# secs_q84_v2.net
KiCad netlist of a schematic drawn in EAGLE
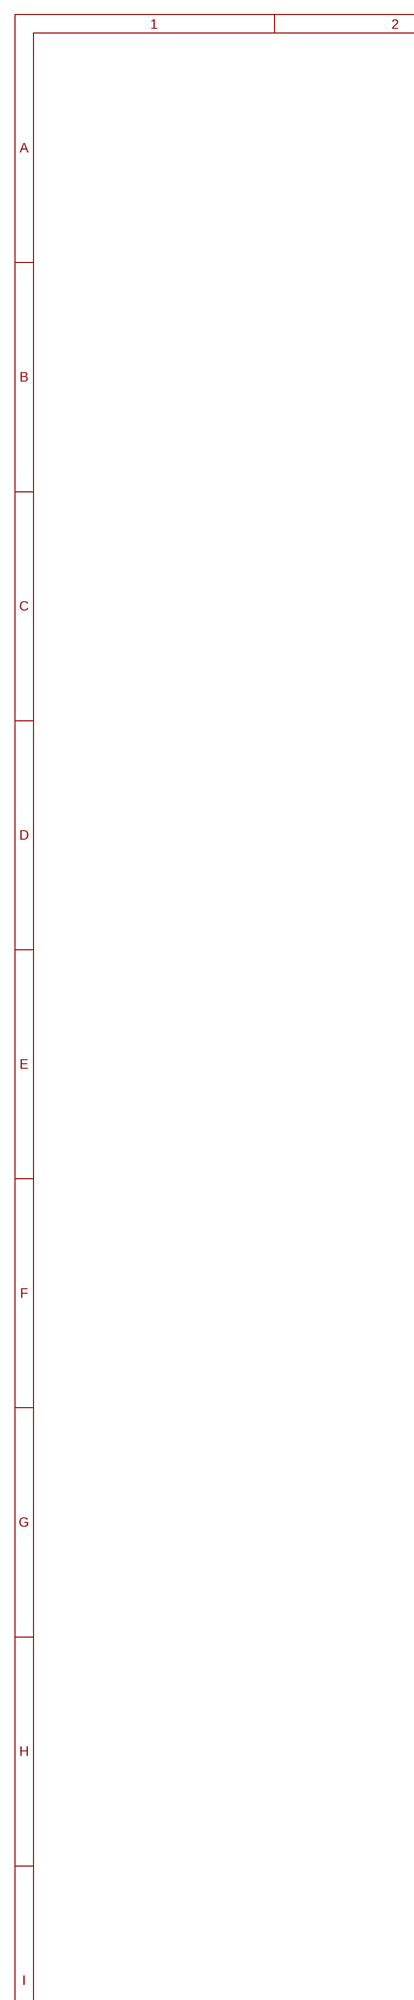
[diagram p0: schematic, sheet 1, part 1 of 2]
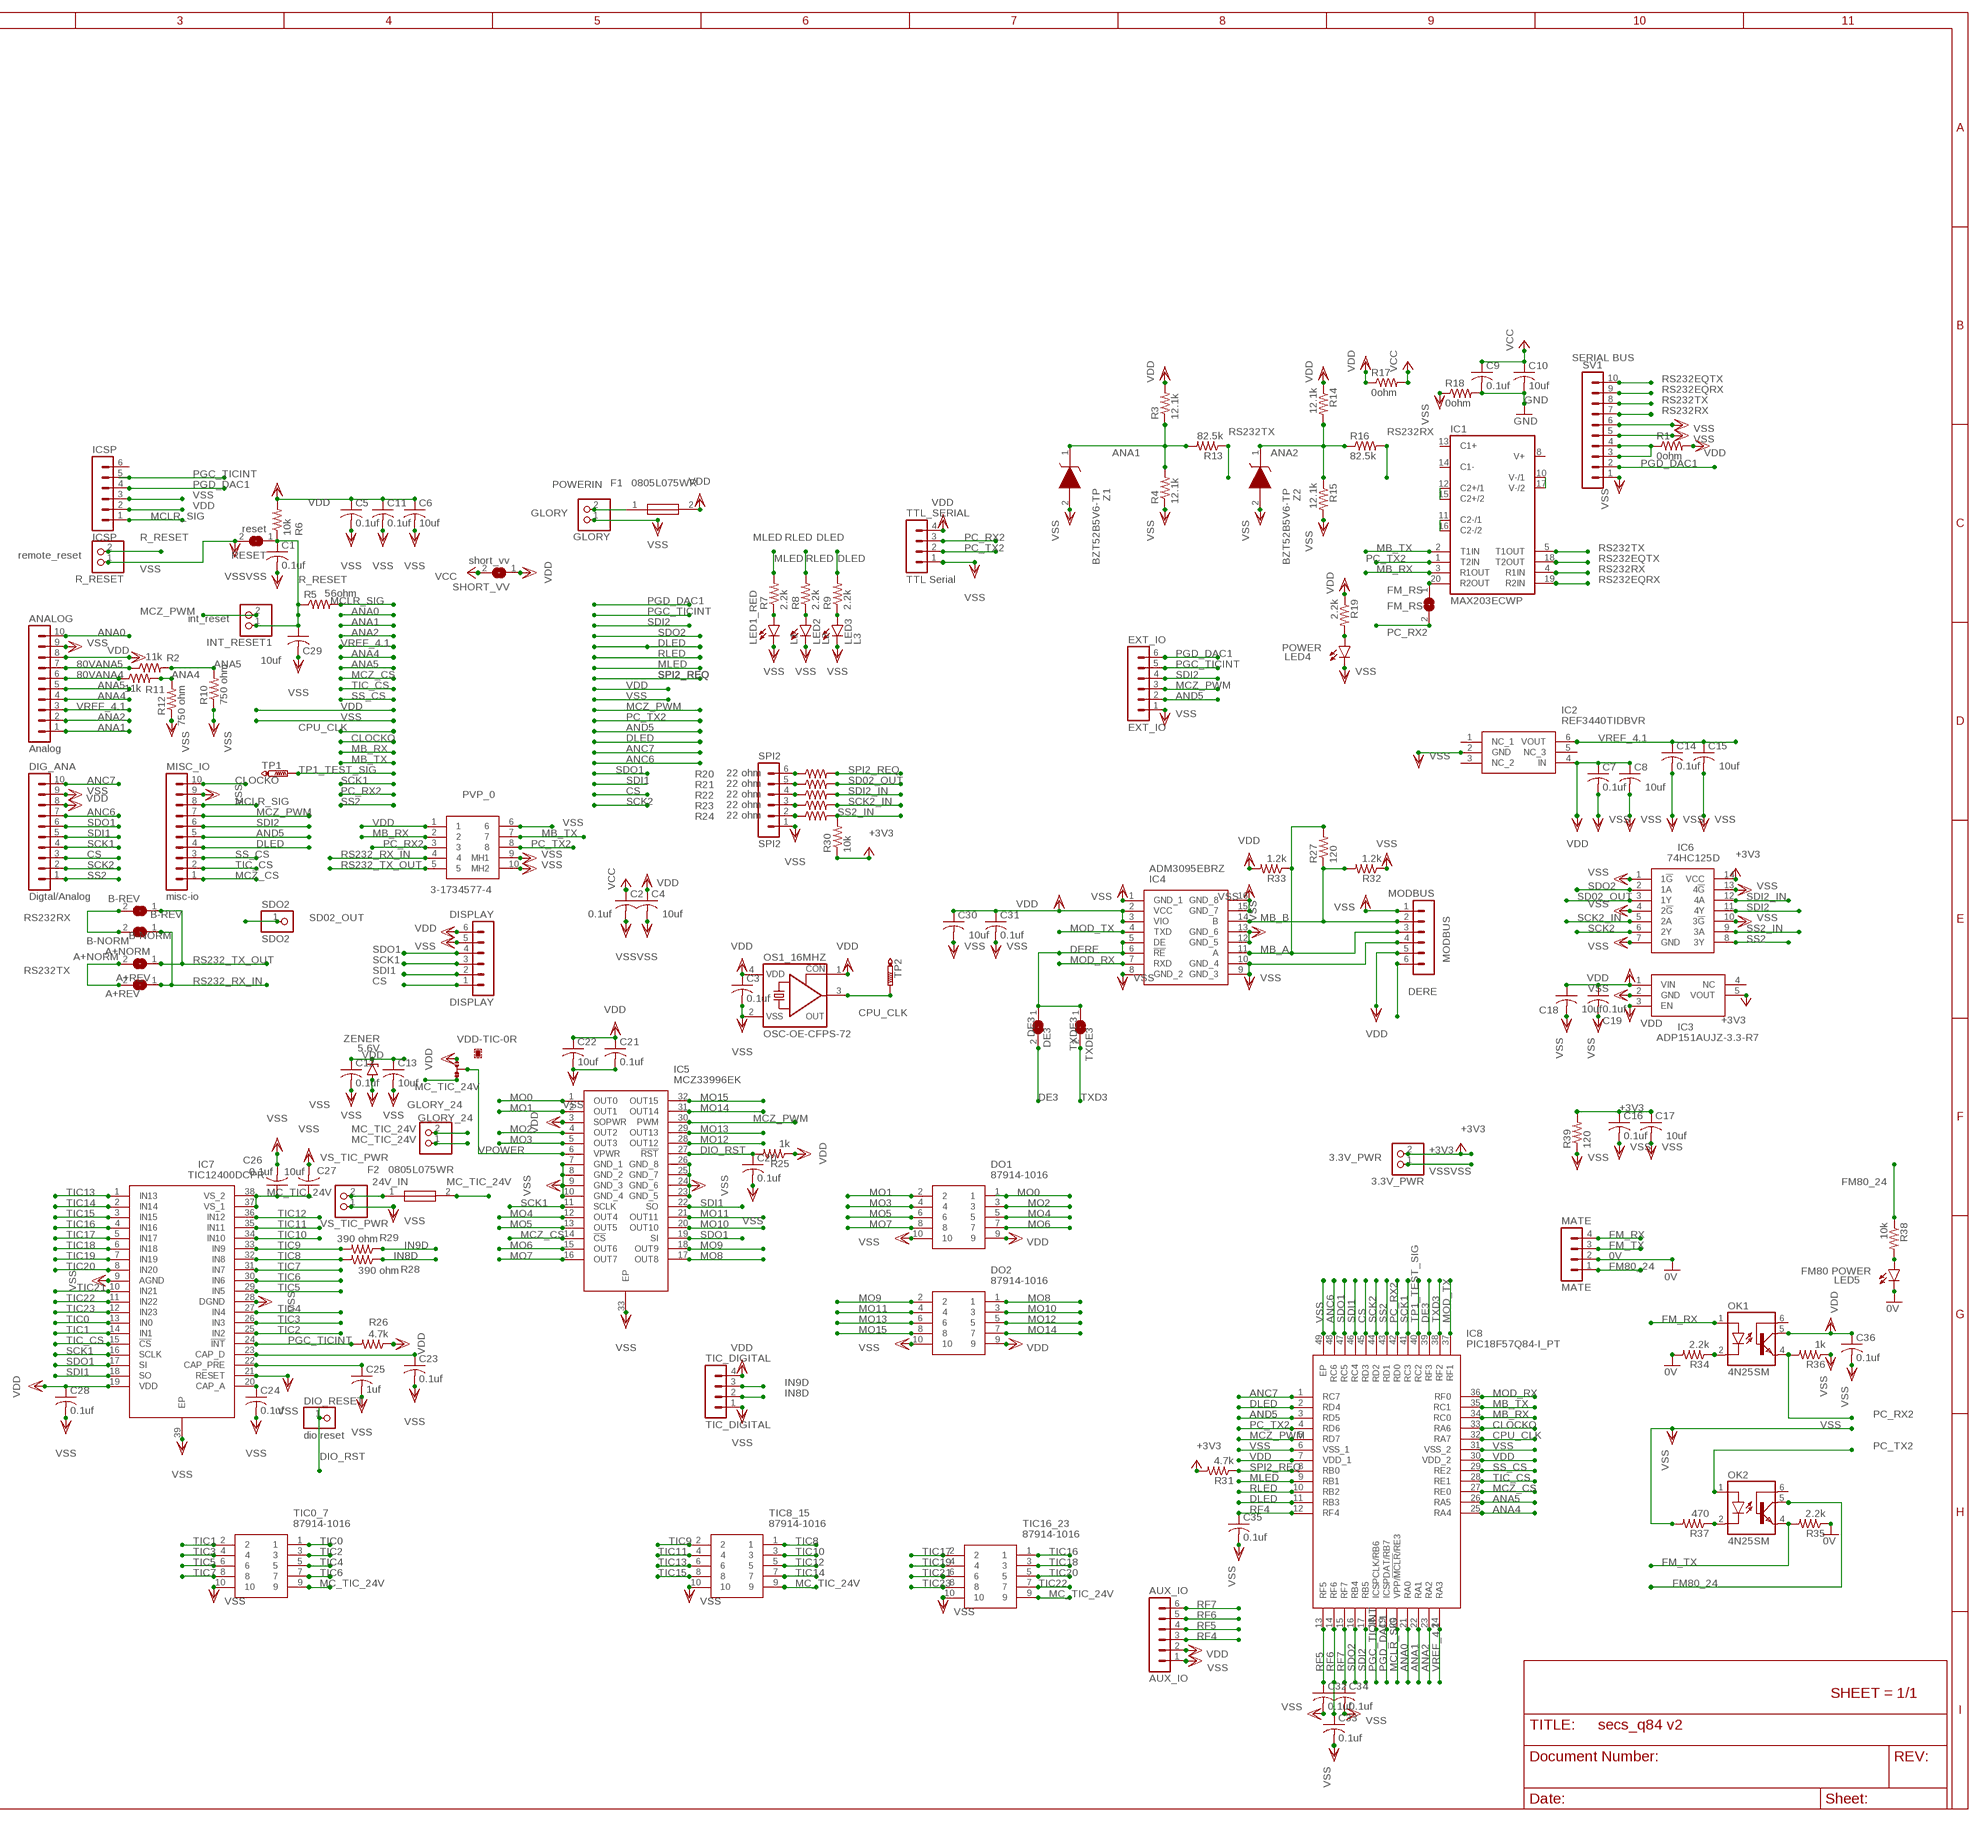
[diagram p1: schematic, sheet 1, part 2 of 2]

(export (version "E")
  (design (tool "Eeschema 10.0.6"))
  (components
    (comp (ref "3.3V_PWR")
      (value "3.3V_PWR")
      (footprint "eagle-import:1X02")
      (libsource (lib "eagle-import") (part "PINHD-1X2"))
    )
    (comp (ref "A+NORM")
      (value "A+NORM")
      (footprint "eagle-import:SJ")
      (libsource (lib "eagle-import") (part "SJ"))
    )
    (comp (ref "A+REV")
      (value "A+REV")
      (footprint "eagle-import:SJ")
      (libsource (lib "eagle-import") (part "SJ"))
    )
    (comp (ref "ANALOG")
      (value "Analog")
      (footprint "eagle-import:MA10-1")
      (libsource (lib "eagle-import") (part "MA10-1"))
    )
    (comp (ref "AUX_IO")
      (value "AUX_IO")
      (footprint "eagle-import:MA06-1")
      (libsource (lib "eagle-import") (part "MA06-1"))
    )
    (comp (ref "B-NORM")
      (value "B-NORM")
      (footprint "eagle-import:SJ")
      (libsource (lib "eagle-import") (part "SJ"))
    )
    (comp (ref "B-REV")
      (value "B-REV")
      (footprint "eagle-import:SJ")
      (libsource (lib "eagle-import") (part "SJ"))
    )
    (comp (ref "C1")
      (value "0.1uf")
      (footprint "eagle-import:C0805")
      (libsource (lib "eagle-import") (part "C-USC0805"))
    )
    (comp (ref "C2")
      (value "0.1uf")
      (footprint "eagle-import:C0805")
      (libsource (lib "eagle-import") (part "C-USC0805"))
    )
    (comp (ref "C3")
      (value "0.1uf")
      (footprint "eagle-import:C0805")
      (libsource (lib "eagle-import") (part "C-USC0805"))
    )
    (comp (ref "C4")
      (value "10uf")
      (footprint "eagle-import:C0805")
      (libsource (lib "eagle-import") (part "C-USC0805"))
    )
    (comp (ref "C5")
      (value "0.1uf")
      (footprint "eagle-import:C0805")
      (libsource (lib "eagle-import") (part "C-USC0805"))
    )
    (comp (ref "C6")
      (value "10uf")
      (footprint "eagle-import:C0805")
      (libsource (lib "eagle-import") (part "C-USC0805"))
    )
    (comp (ref "C7")
      (value "0.1uf")
      (footprint "eagle-import:C0805")
      (libsource (lib "eagle-import") (part "C-USC0805"))
    )
    (comp (ref "C8")
      (value "10uf")
      (footprint "eagle-import:C0805")
      (libsource (lib "eagle-import") (part "C-USC0805"))
    )
    (comp (ref "C9")
      (value "0.1uf")
      (footprint "eagle-import:C0805")
      (libsource (lib "eagle-import") (part "C-USC0805"))
    )
    (comp (ref "C10")
      (value "10uf")
      (footprint "eagle-import:C0805")
      (libsource (lib "eagle-import") (part "C-USC0805"))
    )
    (comp (ref "C11")
      (value "0.1uf")
      (footprint "eagle-import:C0805")
      (libsource (lib "eagle-import") (part "C-USC0805"))
    )
    (comp (ref "C12")
      (value "0.1uf")
      (footprint "eagle-import:C0805")
      (libsource (lib "eagle-import") (part "C-USC0805"))
    )
    (comp (ref "C13")
      (value "10uf")
      (footprint "eagle-import:C0805")
      (libsource (lib "eagle-import") (part "C-USC0805"))
    )
    (comp (ref "C14")
      (value "0.1uf")
      (footprint "eagle-import:C0805")
      (libsource (lib "eagle-import") (part "C-USC0805"))
    )
    (comp (ref "C15")
      (value "10uf")
      (footprint "eagle-import:C0805")
      (libsource (lib "eagle-import") (part "C-USC0805"))
    )
    (comp (ref "C16")
      (value "0.1uf")
      (footprint "eagle-import:C0805")
      (libsource (lib "eagle-import") (part "C-USC0805"))
    )
    (comp (ref "C17")
      (value "10uf")
      (footprint "eagle-import:C0805")
      (libsource (lib "eagle-import") (part "C-USC0805"))
    )
    (comp (ref "C18")
      (value "10uf")
      (footprint "eagle-import:C0805")
      (libsource (lib "eagle-import") (part "C-USC0805"))
    )
    (comp (ref "C19")
      (value "0.1uf")
      (footprint "eagle-import:C0805")
      (libsource (lib "eagle-import") (part "C-USC0805"))
    )
    (comp (ref "C20")
      (value "0.1uf")
      (footprint "eagle-import:C0805")
      (libsource (lib "eagle-import") (part "C-USC0805"))
    )
    (comp (ref "C21")
      (value "0.1uf")
      (footprint "eagle-import:C0805")
      (libsource (lib "eagle-import") (part "C-USC0805"))
    )
    (comp (ref "C22")
      (value "10uf")
      (footprint "eagle-import:C0805")
      (libsource (lib "eagle-import") (part "C-USC0805"))
    )
    (comp (ref "C23")
      (value "0.1uf")
      (footprint "eagle-import:C0805")
      (libsource (lib "eagle-import") (part "C-USC0805"))
    )
    (comp (ref "C24")
      (value "0.1uf")
      (footprint "eagle-import:C0805")
      (libsource (lib "eagle-import") (part "C-USC0805"))
    )
    (comp (ref "C25")
      (value "1uf")
      (footprint "eagle-import:C0805")
      (libsource (lib "eagle-import") (part "C-USC0805"))
    )
    (comp (ref "C26")
      (value "0.1uf")
      (footprint "eagle-import:C0805")
      (libsource (lib "eagle-import") (part "C-USC0805"))
    )
    (comp (ref "C27")
      (value "10uf")
      (footprint "eagle-import:C0805")
      (libsource (lib "eagle-import") (part "C-USC0805"))
    )
    (comp (ref "C28")
      (value "0.1uf")
      (footprint "eagle-import:C0805")
      (libsource (lib "eagle-import") (part "C-USC0805"))
    )
    (comp (ref "C29")
      (value "10uf")
      (footprint "eagle-import:C0805")
      (libsource (lib "eagle-import") (part "C-USC0805"))
    )
    (comp (ref "C30")
      (value "10uf")
      (footprint "eagle-import:C0805")
      (libsource (lib "eagle-import") (part "C-USC0805"))
    )
    (comp (ref "C31")
      (value "0.1uf")
      (footprint "eagle-import:C0805")
      (libsource (lib "eagle-import") (part "C-USC0805"))
    )
    (comp (ref "C32")
      (value "0.1uf")
      (footprint "eagle-import:C0603")
      (libsource (lib "eagle-import") (part "C-USC0603"))
    )
    (comp (ref "C33")
      (value "0.1uf")
      (footprint "eagle-import:C0603")
      (libsource (lib "eagle-import") (part "C-USC0603"))
    )
    (comp (ref "C34")
      (value "0.1uf")
      (footprint "eagle-import:C0603")
      (libsource (lib "eagle-import") (part "C-USC0603"))
    )
    (comp (ref "C35")
      (value "0.1uf")
      (footprint "eagle-import:C0603")
      (libsource (lib "eagle-import") (part "C-USC0603"))
    )
    (comp (ref "C36")
      (value "0.1uf")
      (footprint "eagle-import:C0603")
      (libsource (lib "eagle-import") (part "C-USC0603"))
    )
    (comp (ref "DE3")
      (value "DE3")
      (footprint "eagle-import:SJ")
      (libsource (lib "eagle-import") (part "SJ"))
    )
    (comp (ref "DIG_ANA")
      (value "Digtal/Analog")
      (footprint "eagle-import:MA10-1")
      (libsource (lib "eagle-import") (part "MA10-1"))
    )
    (comp (ref "DIO_RESET")
      (value "dio reset")
      (footprint "eagle-import:1X01")
      (libsource (lib "eagle-import") (part "PINHD-1X1"))
    )
    (comp (ref "DISPLAY")
      (value "DISPLAY")
      (footprint "eagle-import:MA06-1")
      (libsource (lib "eagle-import") (part "MA06-1"))
    )
    (comp (ref "DO1")
      (value "87914-1016")
      (footprint "eagle-import:879141016")
      (fields (field (name "MOUSER_PART_NUMBER") "538-87914-1016"))
      (libsource (lib "eagle-import") (part "87914-1016"))
    )
    (comp (ref "DO2")
      (value "87914-1016")
      (footprint "eagle-import:879141016")
      (fields (field (name "MOUSER_PART_NUMBER") "538-87914-1016"))
      (libsource (lib "eagle-import") (part "87914-1016"))
    )
    (comp (ref "EXT_IO")
      (value "EXT_IO")
      (footprint "eagle-import:MA06-1")
      (libsource (lib "eagle-import") (part "MA06-1"))
    )
    (comp (ref "F1")
      (value "0805L075WR")
      (footprint "eagle-import:FUSC2114X125N")
      (fields (field (name "MOUSER_PART_NUMBER") "576-0805L075WR"))
      (libsource (lib "eagle-import") (part "0805L075WR"))
    )
    (comp (ref "F2")
      (value "0805L075WR")
      (footprint "eagle-import:FUSC2114X125N")
      (fields (field (name "MOUSER_PART_NUMBER") "576-0805L075WR"))
      (libsource (lib "eagle-import") (part "0805L075WR"))
    )
    (comp (ref "FM_RS")
      (value "FM_RS")
      (footprint "eagle-import:SJ")
      (libsource (lib "eagle-import") (part "SJ"))
    )
    (comp (ref "GLORY")
      (value "GLORY")
      (footprint "eagle-import:1X02")
      (libsource (lib "eagle-import") (part "PINHD-1X2"))
    )
    (comp (ref "GLORY_24")
      (value "GLORY_24")
      (footprint "eagle-import:1X02")
      (libsource (lib "eagle-import") (part "PINHD-1X2"))
    )
    (comp (ref "IC1")
      (value "MAX203ECWP")
      (footprint "eagle-import:SO20L")
      (fields (field (name "MPN") "MAX203ECWP+G36"))
      (libsource (lib "eagle-import") (part "MAX203ECWP"))
    )
    (comp (ref "IC2")
      (value "REF3440TIDBVR")
      (footprint "eagle-import:SOT95P280X145-6N")
      (fields (field (name "MOUSER_PART_NUMBER") "595-REF3440TIDBVR"))
      (libsource (lib "eagle-import") (part "REF3440TIDBVR"))
    )
    (comp (ref "IC3")
      (value "ADP151AUJZ-3.3-R7")
      (footprint "eagle-import:SOT95P280X100-5N")
      (fields (field (name "MOUSER_PART_NUMBER") "584-ADP151AUJZ-3.3R7"))
      (libsource (lib "eagle-import") (part "ADP151AUJZ-3.3-R7"))
    )
    (comp (ref "IC4")
      (value "ADM3095EBRZ")
      (footprint "eagle-import:SOIC127P600X175-16N")
      (fields (field (name "MOUSER_PART_NUMBER") "584-ADM3095EBRZ"))
      (libsource (lib "eagle-import") (part "ADM3095EBRZ"))
    )
    (comp (ref "IC5")
      (value "MCZ33996EK")
      (footprint "eagle-import:SOP65P1030X265-33N")
      (fields (field (name "MOUSER_PART_NUMBER") "841-MCZ33996EK"))
      (libsource (lib "eagle-import") (part "MCZ33996EK"))
    )
    (comp (ref "IC6")
      (value "74HC125D")
      (footprint "eagle-import:SOIC127P600X175-14N")
      (fields (field (name "MOUSER_PART_NUMBER") "757-74HC125D"))
      (libsource (lib "eagle-import") (part "74HC125D"))
    )
    (comp (ref "IC7")
      (value "TIC12400DCPR")
      (footprint "eagle-import:SOP50P640X120-39N")
      (fields (field (name "MOUSER_PART_NUMBER") "595-TIC12400DCPR"))
      (libsource (lib "eagle-import") (part "TIC12400DCPR"))
    )
    (comp (ref "IC8")
      (value "PIC18F57Q84-I_PT")
      (footprint "eagle-import:QFP50P900X900X120-49N")
      (fields
        (field (name "MANUFACTURER_PART_NUMBER") "PIC18F57Q84-I/PT")
        (field (name "MOUSER_PART_NUMBER") "579-PIC18F57Q84-I/PT")
      )
      (libsource (lib "eagle-import") (part "PIC18F57Q84-I_PT"))
    )
    (comp (ref "ICSP")
      (value "ICSP")
      (footprint "eagle-import:MA06-1")
      (libsource (lib "eagle-import") (part "MA06-1"))
    )
    (comp (ref "INT_RESET1")
      (value "int_reset")
      (footprint "eagle-import:1X02")
      (libsource (lib "eagle-import") (part "PINHD-1X2"))
    )
    (comp (ref "LED1_RED")
      (value "L1")
      (footprint "eagle-import:CHIPLED_0805")
      (libsource (lib "eagle-import") (part "LEDCHIPLED_0805"))
    )
    (comp (ref "LED2")
      (value "L2")
      (footprint "eagle-import:CHIPLED_0805")
      (libsource (lib "eagle-import") (part "LEDCHIPLED_0805"))
    )
    (comp (ref "LED3")
      (value "L3")
      (footprint "eagle-import:CHIPLED_0805")
      (libsource (lib "eagle-import") (part "LEDCHIPLED_0805"))
    )
    (comp (ref "LED4")
      (value "POWER")
      (footprint "eagle-import:CHIP-LED0603")
      (libsource (lib "eagle-import") (part "LEDCHIP-LED0603"))
    )
    (comp (ref "LED5")
      (value "FM80 POWER")
      (footprint "eagle-import:CHIP-LED0603")
      (libsource (lib "eagle-import") (part "LEDCHIP-LED0603"))
    )
    (comp (ref "MATE")
      (value "MATE")
      (footprint "eagle-import:MA04-1")
      (libsource (lib "eagle-import") (part "MA04-1"))
    )
    (comp (ref "MISC_IO")
      (value "misc-io")
      (footprint "eagle-import:MA10-1")
      (libsource (lib "eagle-import") (part "MA10-1"))
    )
    (comp (ref "MODBUS")
      (value "MODBUS")
      (footprint "eagle-import:MA06-1")
      (libsource (lib "eagle-import") (part "MA06-1"))
    )
    (comp (ref "OK1")
      (value "4N25SM")
      (footprint "eagle-import:DIL6-SMD")
      (fields (field (name "MF") "FAIRCHILD SEMICONDUCTOR"))
      (libsource (lib "eagle-import") (part "4N?MS25"))
    )
    (comp (ref "OK2")
      (value "4N25SM")
      (footprint "eagle-import:DIL6-SMD")
      (fields (field (name "MF") "FAIRCHILD SEMICONDUCTOR"))
      (libsource (lib "eagle-import") (part "4N?MS25"))
    )
    (comp (ref "OS1_16MHZ")
      (value "OSC-OE-CFPS-72")
      (footprint "eagle-import:7.2X5.2-4-PAD")
      (libsource (lib "eagle-import") (part "OSC-OE-CFPS-72"))
    )
    (comp (ref "PVP_0")
      (value "3-1734577-4")
      (footprint "eagle-import:317345774")
      (fields (field (name "MOUSER_PART_NUMBER") "571-3-1734577-4"))
      (libsource (lib "eagle-import") (part "3-1734577-4"))
    )
    (comp (ref "R1")
      (value "0ohm")
      (footprint "eagle-import:R0805")
      (libsource (lib "eagle-import") (part "R-US_R0805"))
    )
    (comp (ref "R2")
      (value "11k")
      (footprint "eagle-import:M1206")
      (libsource (lib "eagle-import") (part "R-US_M1206"))
    )
    (comp (ref "R3")
      (value "12.1k")
      (footprint "eagle-import:R0805")
      (libsource (lib "eagle-import") (part "R-US_R0805"))
    )
    (comp (ref "R4")
      (value "12.1k")
      (footprint "eagle-import:R0805")
      (libsource (lib "eagle-import") (part "R-US_R0805"))
    )
    (comp (ref "R5")
      (value "56ohm")
      (footprint "eagle-import:R0805")
      (libsource (lib "eagle-import") (part "R-US_R0805"))
    )
    (comp (ref "R6")
      (value "10k")
      (footprint "eagle-import:R0805")
      (libsource (lib "eagle-import") (part "R-US_R0805"))
    )
    (comp (ref "R7")
      (value "2.2k")
      (footprint "eagle-import:R0805")
      (libsource (lib "eagle-import") (part "R-US_R0805"))
    )
    (comp (ref "R8")
      (value "2.2k")
      (footprint "eagle-import:R0805")
      (libsource (lib "eagle-import") (part "R-US_R0805"))
    )
    (comp (ref "R9")
      (value "2.2k")
      (footprint "eagle-import:R0805")
      (libsource (lib "eagle-import") (part "R-US_R0805"))
    )
    (comp (ref "R10")
      (value "750 ohm")
      (footprint "eagle-import:M1206")
      (libsource (lib "eagle-import") (part "R-US_M1206"))
    )
    (comp (ref "R11")
      (value "11k")
      (footprint "eagle-import:M1206")
      (libsource (lib "eagle-import") (part "R-US_M1206"))
    )
    (comp (ref "R12")
      (value "750 ohm")
      (footprint "eagle-import:M1206")
      (libsource (lib "eagle-import") (part "R-US_M1206"))
    )
    (comp (ref "R13")
      (value "82.5k")
      (footprint "eagle-import:R0805")
      (libsource (lib "eagle-import") (part "R-US_R0805"))
    )
    (comp (ref "R14")
      (value "12.1k")
      (footprint "eagle-import:R0805")
      (libsource (lib "eagle-import") (part "R-US_R0805"))
    )
    (comp (ref "R15")
      (value "12.1k")
      (footprint "eagle-import:R0805")
      (libsource (lib "eagle-import") (part "R-US_R0805"))
    )
    (comp (ref "R16")
      (value "82.5k")
      (footprint "eagle-import:R0805")
      (libsource (lib "eagle-import") (part "R-US_R0805"))
    )
    (comp (ref "R17")
      (value "0ohm")
      (footprint "eagle-import:R0805")
      (libsource (lib "eagle-import") (part "R-US_R0805"))
    )
    (comp (ref "R18")
      (value "0ohm")
      (footprint "eagle-import:R0805")
      (libsource (lib "eagle-import") (part "R-US_R0805"))
    )
    (comp (ref "R19")
      (value "2.2k")
      (footprint "eagle-import:R0805")
      (libsource (lib "eagle-import") (part "R-US_R0805"))
    )
    (comp (ref "R20")
      (value "22 ohm")
      (footprint "eagle-import:R0805")
      (libsource (lib "eagle-import") (part "R-US_R0805"))
    )
    (comp (ref "R21")
      (value "22 ohm")
      (footprint "eagle-import:R0805")
      (libsource (lib "eagle-import") (part "R-US_R0805"))
    )
    (comp (ref "R22")
      (value "22 ohm")
      (footprint "eagle-import:R0805")
      (libsource (lib "eagle-import") (part "R-US_R0805"))
    )
    (comp (ref "R23")
      (value "22 ohm")
      (footprint "eagle-import:R0805")
      (libsource (lib "eagle-import") (part "R-US_R0805"))
    )
    (comp (ref "R24")
      (value "22 ohm")
      (footprint "eagle-import:R0805")
      (libsource (lib "eagle-import") (part "R-US_R0805"))
    )
    (comp (ref "R25")
      (value "1k")
      (footprint "eagle-import:R0805")
      (libsource (lib "eagle-import") (part "R-US_R0805"))
    )
    (comp (ref "R26")
      (value "4.7k")
      (footprint "eagle-import:R0805")
      (libsource (lib "eagle-import") (part "R-US_R0805"))
    )
    (comp (ref "R27")
      (value "120")
      (footprint "eagle-import:R0805")
      (libsource (lib "eagle-import") (part "R-US_R0805"))
    )
    (comp (ref "R28")
      (value "390 ohm")
      (footprint "eagle-import:R0805")
      (libsource (lib "eagle-import") (part "R-US_R0805"))
    )
    (comp (ref "R29")
      (value "390 ohm")
      (footprint "eagle-import:R0805")
      (libsource (lib "eagle-import") (part "R-US_R0805"))
    )
    (comp (ref "R30")
      (value "10k")
      (footprint "eagle-import:R0805")
      (libsource (lib "eagle-import") (part "R-US_R0805"))
    )
    (comp (ref "R31")
      (value "4.7k")
      (footprint "eagle-import:R0805")
      (libsource (lib "eagle-import") (part "R-US_R0805"))
    )
    (comp (ref "R32")
      (value "1.2k")
      (footprint "eagle-import:R0805")
      (libsource (lib "eagle-import") (part "R-US_R0805"))
    )
    (comp (ref "R33")
      (value "1.2k")
      (footprint "eagle-import:R0805")
      (libsource (lib "eagle-import") (part "R-US_R0805"))
    )
    (comp (ref "R34")
      (value "2.2k")
      (footprint "eagle-import:R0805")
      (libsource (lib "eagle-import") (part "R-US_R0805"))
    )
    (comp (ref "R35")
      (value "2.2k")
      (footprint "eagle-import:R0805")
      (libsource (lib "eagle-import") (part "R-US_R0805"))
    )
    (comp (ref "R36")
      (value "1k")
      (footprint "eagle-import:R0805")
      (libsource (lib "eagle-import") (part "R-US_R0805"))
    )
    (comp (ref "R37")
      (value "470")
      (footprint "eagle-import:R0805")
      (libsource (lib "eagle-import") (part "R-US_R0805"))
    )
    (comp (ref "R38")
      (value "10k")
      (footprint "eagle-import:R0805")
      (libsource (lib "eagle-import") (part "R-US_R0805"))
    )
    (comp (ref "R39")
      (value "120")
      (footprint "eagle-import:R0805")
      (libsource (lib "eagle-import") (part "R-US_R0805"))
    )
    (comp (ref "RESET")
      (value "reset")
      (footprint "eagle-import:SJ")
      (libsource (lib "eagle-import") (part "SJ"))
    )
    (comp (ref "R_RESET")
      (value "remote_reset")
      (footprint "eagle-import:1X02")
      (libsource (lib "eagle-import") (part "PINHD-1X2"))
    )
    (comp (ref "SDO2")
      (value "SDO2")
      (footprint "eagle-import:1X01")
      (libsource (lib "eagle-import") (part "PINHD-1X1"))
    )
    (comp (ref "SHORT_VV")
      (value "short_vv")
      (footprint "eagle-import:SJ")
      (libsource (lib "eagle-import") (part "SJ"))
    )
    (comp (ref "SPI2")
      (value "SPI2")
      (footprint "eagle-import:MA06-1")
      (libsource (lib "eagle-import") (part "MA06-1"))
    )
    (comp (ref "SV1")
      (value "SERIAL BUS")
      (footprint "eagle-import:MA10-1")
      (libsource (lib "eagle-import") (part "MA10-1"))
    )
    (comp (ref "TIC0_7")
      (value "87914-1016")
      (footprint "eagle-import:879141016")
      (fields (field (name "MOUSER_PART_NUMBER") "538-87914-1016"))
      (libsource (lib "eagle-import") (part "87914-1016"))
    )
    (comp (ref "TIC8_15")
      (value "87914-1016")
      (footprint "eagle-import:879141016")
      (fields (field (name "MOUSER_PART_NUMBER") "538-87914-1016"))
      (libsource (lib "eagle-import") (part "87914-1016"))
    )
    (comp (ref "TIC16_23")
      (value "87914-1016")
      (footprint "eagle-import:879141016")
      (fields (field (name "MOUSER_PART_NUMBER") "538-87914-1016"))
      (libsource (lib "eagle-import") (part "87914-1016"))
    )
    (comp (ref "TIC_DIGITAL")
      (value "TIC_DIGITAL")
      (footprint "eagle-import:MA04-1")
      (libsource (lib "eagle-import") (part "MA04-1"))
    )
    (comp (ref "TP1")
      (value "PTR1PAD1-13")
      (footprint "eagle-import:P1-13")
      (libsource (lib "eagle-import") (part "PTR1PAD1-13"))
    )
    (comp (ref "TP2")
      (value "PTR1PAD1-13")
      (footprint "eagle-import:P1-13")
      (libsource (lib "eagle-import") (part "PTR1PAD1-13"))
    )
    (comp (ref "TTL_SERIAL")
      (value "TTL Serial")
      (footprint "eagle-import:MA04-1")
      (libsource (lib "eagle-import") (part "MA04-1"))
    )
    (comp (ref "TXDE3")
      (value "TXDE3")
      (footprint "eagle-import:SJ")
      (libsource (lib "eagle-import") (part "SJ"))
    )
    (comp (ref "VDD-TIC")
      (value "0R-JUMPA")
      (footprint "eagle-import:A0R-JMP")
      (libsource (lib "eagle-import") (part "0R-JUMPA"))
    )
    (comp (ref "VS_TIC_PWR")
      (value "VS_TIC_PWR")
      (footprint "eagle-import:1X02")
      (libsource (lib "eagle-import") (part "PINHD-1X2"))
    )
    (comp (ref "Z1")
      (value "BZT52B5V6-TP")
      (footprint "eagle-import:SOD3716X135N")
      (fields (field (name "MOUSER_PART_NUMBER") "833-BZT52B5V6-TP"))
      (libsource (lib "eagle-import") (part "BZT52B5V6-TP"))
    )
    (comp (ref "Z2")
      (value "BZT52B5V6-TP")
      (footprint "eagle-import:SOD3716X135N")
      (fields (field (name "MOUSER_PART_NUMBER") "833-BZT52B5V6-TP"))
      (libsource (lib "eagle-import") (part "BZT52B5V6-TP"))
    )
    (comp (ref "ZENER")
      (value "5.6V")
      (footprint "eagle-import:SMB")
      (libsource (lib "eagle-import") (part "ZENER-DIODESMB"))
    )
  )
  (nets
    (net (code "1") (name "+3V3") (class "Default")
      (node (ref "3.3V_PWR") (pin "2") (pinfunction "2_2") (pintype "passive"))
      (node (ref "C16") (pin "1") (pinfunction "1_1") (pintype "passive"))
      (node (ref "C17") (pin "1") (pinfunction "1_1") (pintype "passive"))
      (node (ref "IC3") (pin "5") (pinfunction "VOUT_5") (pintype "bidirectional"))
      (node (ref "IC6") (pin "14") (pinfunction "VCC_14") (pintype "bidirectional"))
      (node (ref "R30") (pin "1") (pinfunction "1_1") (pintype "passive"))
      (node (ref "R31") (pin "2") (pinfunction "2_2") (pintype "passive"))
      (node (ref "R39") (pin "2") (pinfunction "2_2") (pintype "passive"))
    )
    (net (code "2") (name "/24V_IN") (class "Default")
      (node (ref "F2") (pin "1") (pinfunction "1_1") (pintype "bidirectional"))
      (node (ref "VS_TIC_PWR") (pin "2") (pinfunction "2_2") (pintype "passive"))
    )
    (net (code "3") (name "/80VANA4") (class "Default")
      (node (ref "ANALOG") (pin "6") (pinfunction "6_6") (pintype "passive"))
      (node (ref "R11") (pin "1") (pinfunction "1_1") (pintype "passive"))
    )
    (net (code "4") (name "/80VANA5") (class "Default")
      (node (ref "ANALOG") (pin "7") (pinfunction "7_7") (pintype "passive"))
      (node (ref "R2") (pin "1") (pinfunction "1_1") (pintype "passive"))
    )
    (net (code "5") (name "/ANA0") (class "Default")
      (node (ref "ANALOG") (pin "10") (pinfunction "10_10") (pintype "passive"))
      (node (ref "IC8") (pin "21") (pinfunction "RA0_21") (pintype "bidirectional"))
    )
    (net (code "6") (name "/ANA1") (class "Default")
      (node (ref "ANALOG") (pin "1") (pinfunction "1_1") (pintype "passive"))
      (node (ref "IC8") (pin "22") (pinfunction "RA1_22") (pintype "bidirectional"))
      (node (ref "R13") (pin "2") (pinfunction "2_2") (pintype "passive"))
      (node (ref "R3") (pin "1") (pinfunction "1_1") (pintype "passive"))
      (node (ref "R4") (pin "2") (pinfunction "2_2") (pintype "passive"))
      (node (ref "Z1") (pin "1") (pinfunction "K_1") (pintype "bidirectional"))
    )
    (net (code "7") (name "/ANA2") (class "Default")
      (node (ref "ANALOG") (pin "2") (pinfunction "2_2") (pintype "passive"))
      (node (ref "IC8") (pin "23") (pinfunction "RA2_23") (pintype "bidirectional"))
      (node (ref "R14") (pin "2") (pinfunction "2_2") (pintype "passive"))
      (node (ref "R15") (pin "1") (pinfunction "1_1") (pintype "passive"))
      (node (ref "R16") (pin "1") (pinfunction "1_1") (pintype "passive"))
      (node (ref "Z2") (pin "1") (pinfunction "K_1") (pintype "bidirectional"))
    )
    (net (code "8") (name "/ANA4") (class "Default")
      (node (ref "ANALOG") (pin "4") (pinfunction "4_4") (pintype "passive"))
      (node (ref "IC8") (pin "25") (pinfunction "RA4_25") (pintype "bidirectional"))
      (node (ref "R11") (pin "2") (pinfunction "2_2") (pintype "passive"))
      (node (ref "R12") (pin "2") (pinfunction "2_2") (pintype "passive"))
    )
    (net (code "9") (name "/ANA5") (class "Default")
      (node (ref "ANALOG") (pin "5") (pinfunction "5_5") (pintype "passive"))
      (node (ref "IC8") (pin "26") (pinfunction "RA5_26") (pintype "bidirectional"))
      (node (ref "R10") (pin "2") (pinfunction "2_2") (pintype "passive"))
      (node (ref "R2") (pin "2") (pinfunction "2_2") (pintype "passive"))
    )
    (net (code "10") (name "/ANC6") (class "Default")
      (node (ref "DIG_ANA") (pin "7") (pinfunction "7_7") (pintype "passive"))
      (node (ref "IC8") (pin "48") (pinfunction "RC6_48") (pintype "bidirectional"))
    )
    (net (code "11") (name "/ANC7") (class "Default")
      (node (ref "DIG_ANA") (pin "10") (pinfunction "10_10") (pintype "passive"))
      (node (ref "IC8") (pin "1") (pinfunction "RC7_1") (pintype "bidirectional"))
    )
    (net (code "12") (name "/AND5") (class "Default")
      (node (ref "EXT_IO") (pin "2") (pinfunction "2_2") (pintype "passive"))
      (node (ref "IC8") (pin "3") (pinfunction "RD5_3") (pintype "bidirectional"))
      (node (ref "MISC_IO") (pin "5") (pinfunction "5_5") (pintype "passive"))
    )
    (net (code "13") (name "/CLOCKO") (class "Default")
      (node (ref "IC8") (pin "33") (pinfunction "RA6_33") (pintype "bidirectional"))
      (node (ref "MISC_IO") (pin "10") (pinfunction "10_10") (pintype "passive"))
    )
    (net (code "14") (name "/CPU_CLK") (class "Default")
      (node (ref "IC8") (pin "32") (pinfunction "RA7_32") (pintype "bidirectional"))
      (node (ref "OS1_16MHZ") (pin "3") (pinfunction "OUT_3") (pintype "output"))
      (node (ref "TP2") (pin "TP") (pinfunction "TP_TP") (pintype "input"))
    )
    (net (code "15") (name "/CS") (class "Default")
      (node (ref "DIG_ANA") (pin "3") (pinfunction "3_3") (pintype "passive"))
      (node (ref "DISPLAY") (pin "1") (pinfunction "1_1") (pintype "passive"))
      (node (ref "IC8") (pin "45") (pinfunction "RD3_45") (pintype "bidirectional"))
    )
    (net (code "16") (name "/DE3") (class "Default")
      (node (ref "DE3") (pin "2") (pinfunction "2_2") (pintype "passive"))
      (node (ref "IC8") (pin "39") (pinfunction "RF3_39") (pintype "bidirectional"))
    )
    (net (code "17") (name "/DERE") (class "Default")
      (node (ref "DE3") (pin "1") (pinfunction "1_1") (pintype "passive"))
      (node (ref "IC4") (pin "5") (pinfunction "DE_5") (pintype "input"))
      (node (ref "IC4") (pin "6") (pinfunction "~{RE}_6") (pintype "input"))
      (node (ref "MODBUS") (pin "6") (pinfunction "6_6") (pintype "passive"))
      (node (ref "TXDE3") (pin "1") (pinfunction "1_1") (pintype "passive"))
    )
    (net (code "18") (name "/DIO_RST") (class "Default")
      (node (ref "C20") (pin "1") (pinfunction "1_1") (pintype "passive"))
      (node (ref "DIO_RESET") (pin "1") (pinfunction "1_1") (pintype "passive"))
      (node (ref "IC5") (pin "27") (pinfunction "~{RST}_27") (pintype "bidirectional"))
      (node (ref "R25") (pin "2") (pinfunction "2_2") (pintype "passive"))
    )
    (net (code "19") (name "/DLED") (class "Default")
      (node (ref "IC8") (pin "11") (pinfunction "RB3_11") (pintype "bidirectional"))
      (node (ref "IC8") (pin "2") (pinfunction "RD4_2") (pintype "bidirectional"))
      (node (ref "MISC_IO") (pin "4") (pinfunction "4_4") (pintype "passive"))
      (node (ref "R9") (pin "2") (pinfunction "2_2") (pintype "passive"))
    )
    (net (code "20") (name "/FM80_24") (class "Default")
      (node (ref "MATE") (pin "1") (pinfunction "1_1") (pintype "passive"))
      (node (ref "OK2") (pin "5") (pinfunction "COL_5") (pintype "passive"))
      (node (ref "R38") (pin "1") (pinfunction "1_1") (pintype "passive"))
    )
    (net (code "21") (name "/FM_RX") (class "Default")
      (node (ref "MATE") (pin "4") (pinfunction "4_4") (pintype "passive"))
      (node (ref "OK1") (pin "1") (pinfunction "A_1") (pintype "passive"))
    )
    (net (code "22") (name "/FM_TX") (class "Default")
      (node (ref "MATE") (pin "3") (pinfunction "3_3") (pintype "passive"))
      (node (ref "OK2") (pin "4") (pinfunction "EMI_4") (pintype "passive"))
      (node (ref "R35") (pin "2") (pinfunction "2_2") (pintype "passive"))
    )
    (net (code "23") (name "/IN8D") (class "Default")
      (node (ref "R28") (pin "1") (pinfunction "1_1") (pintype "passive"))
      (node (ref "TIC_DIGITAL") (pin "2") (pinfunction "2_2") (pintype "passive"))
    )
    (net (code "24") (name "/IN9D") (class "Default")
      (node (ref "R29") (pin "1") (pinfunction "1_1") (pintype "passive"))
      (node (ref "TIC_DIGITAL") (pin "3") (pinfunction "3_3") (pintype "passive"))
    )
    (net (code "25") (name "/MB_A") (class "Default")
      (node (ref "IC4") (pin "11") (pinfunction "A_11") (pintype "bidirectional"))
      (node (ref "MODBUS") (pin "3") (pinfunction "3_3") (pintype "passive"))
      (node (ref "R27") (pin "2") (pinfunction "2_2") (pintype "passive"))
      (node (ref "R33") (pin "1") (pinfunction "1_1") (pintype "passive"))
    )
    (net (code "26") (name "/MB_B") (class "Default")
      (node (ref "IC4") (pin "14") (pinfunction "B_14") (pintype "bidirectional"))
      (node (ref "MODBUS") (pin "2") (pinfunction "2_2") (pintype "passive"))
      (node (ref "R27") (pin "1") (pinfunction "1_1") (pintype "passive"))
      (node (ref "R32") (pin "2") (pinfunction "2_2") (pintype "passive"))
    )
    (net (code "27") (name "/MB_RX") (class "Default")
      (node (ref "IC1") (pin "3") (pinfunction "R1OUT_3") (pintype "output"))
      (node (ref "IC8") (pin "34") (pinfunction "RC0_34") (pintype "bidirectional"))
      (node (ref "PVP_0") (pin "2") (pinfunction "2_2") (pintype "bidirectional"))
    )
    (net (code "28") (name "/MB_TX") (class "Default")
      (node (ref "IC1") (pin "2") (pinfunction "T1IN_2") (pintype "input"))
      (node (ref "IC8") (pin "35") (pinfunction "RC1_35") (pintype "bidirectional"))
      (node (ref "PVP_0") (pin "7") (pinfunction "7_7") (pintype "bidirectional"))
    )
    (net (code "29") (name "/MCLR_SIG") (class "Default")
      (node (ref "IC8") (pin "20") (pinfunction "VPP/~{MCLR}/RE3_20") (pintype "bidirectional"))
      (node (ref "ICSP") (pin "1") (pinfunction "1_1") (pintype "passive"))
      (node (ref "MISC_IO") (pin "8") (pinfunction "8_8") (pintype "passive"))
      (node (ref "R5") (pin "2") (pinfunction "2_2") (pintype "passive"))
    )
    (net (code "30") (name "/MCZ_CS") (class "Default")
      (node (ref "IC5") (pin "14") (pinfunction "~{CS}_14") (pintype "bidirectional"))
      (node (ref "IC8") (pin "27") (pinfunction "RE0_27") (pintype "bidirectional"))
      (node (ref "MISC_IO") (pin "1") (pinfunction "1_1") (pintype "passive"))
    )
    (net (code "31") (name "/MCZ_PWM") (class "Default")
      (node (ref "EXT_IO") (pin "3") (pinfunction "3_3") (pintype "passive"))
      (node (ref "IC5") (pin "30") (pinfunction "PWM_30") (pintype "bidirectional"))
      (node (ref "IC8") (pin "5") (pinfunction "RD7_5") (pintype "bidirectional"))
      (node (ref "INT_RESET1") (pin "2") (pinfunction "2_2") (pintype "passive"))
      (node (ref "MISC_IO") (pin "7") (pinfunction "7_7") (pintype "passive"))
    )
    (net (code "32") (name "/MC_TIC_24V") (class "Default")
      (node (ref "C26") (pin "1") (pinfunction "1_1") (pintype "passive"))
      (node (ref "C27") (pin "1") (pinfunction "1_1") (pintype "passive"))
      (node (ref "F2") (pin "2") (pinfunction "2_2") (pintype "bidirectional"))
      (node (ref "GLORY_24") (pin "1") (pinfunction "1_1") (pintype "passive"))
      (node (ref "GLORY_24") (pin "2") (pinfunction "2_2") (pintype "passive"))
      (node (ref "IC7") (pin "37") (pinfunction "VS_1_37") (pintype "bidirectional"))
      (node (ref "IC7") (pin "38") (pinfunction "VS_2_38") (pintype "bidirectional"))
      (node (ref "TIC0_7") (pin "9") (pinfunction "9_9") (pintype "bidirectional"))
      (node (ref "TIC16_23") (pin "9") (pinfunction "9_9") (pintype "bidirectional"))
      (node (ref "TIC8_15") (pin "9") (pinfunction "9_9") (pintype "bidirectional"))
      (node (ref "VDD-TIC") (pin "3") (pinfunction "3_3") (pintype "passive"))
    )
    (net (code "33") (name "/MLED") (class "Default")
      (node (ref "IC8") (pin "9") (pinfunction "RB1_9") (pintype "bidirectional"))
      (node (ref "R7") (pin "2") (pinfunction "2_2") (pintype "passive"))
    )
    (net (code "34") (name "/MO0") (class "Default")
      (node (ref "DO1") (pin "1") (pinfunction "1_1") (pintype "bidirectional"))
      (node (ref "IC5") (pin "1") (pinfunction "OUT0_1") (pintype "bidirectional"))
    )
    (net (code "35") (name "/MO1") (class "Default")
      (node (ref "DO1") (pin "2") (pinfunction "2_2") (pintype "bidirectional"))
      (node (ref "IC5") (pin "2") (pinfunction "OUT1_2") (pintype "bidirectional"))
    )
    (net (code "36") (name "/MO2") (class "Default")
      (node (ref "DO1") (pin "3") (pinfunction "3_3") (pintype "bidirectional"))
      (node (ref "IC5") (pin "4") (pinfunction "OUT2_4") (pintype "bidirectional"))
    )
    (net (code "37") (name "/MO3") (class "Default")
      (node (ref "DO1") (pin "4") (pinfunction "4_4") (pintype "bidirectional"))
      (node (ref "IC5") (pin "5") (pinfunction "OUT3_5") (pintype "bidirectional"))
    )
    (net (code "38") (name "/MO4") (class "Default")
      (node (ref "DO1") (pin "5") (pinfunction "5_5") (pintype "bidirectional"))
      (node (ref "IC5") (pin "12") (pinfunction "OUT4_12") (pintype "bidirectional"))
    )
    (net (code "39") (name "/MO5") (class "Default")
      (node (ref "DO1") (pin "6") (pinfunction "6_6") (pintype "bidirectional"))
      (node (ref "IC5") (pin "13") (pinfunction "OUT5_13") (pintype "bidirectional"))
    )
    (net (code "40") (name "/MO6") (class "Default")
      (node (ref "DO1") (pin "7") (pinfunction "7_7") (pintype "bidirectional"))
      (node (ref "IC5") (pin "15") (pinfunction "OUT6_15") (pintype "bidirectional"))
    )
    (net (code "41") (name "/MO7") (class "Default")
      (node (ref "DO1") (pin "8") (pinfunction "8_8") (pintype "bidirectional"))
      (node (ref "IC5") (pin "16") (pinfunction "OUT7_16") (pintype "bidirectional"))
    )
    (net (code "42") (name "/MO8") (class "Default")
      (node (ref "DO2") (pin "1") (pinfunction "1_1") (pintype "bidirectional"))
      (node (ref "IC5") (pin "17") (pinfunction "OUT8_17") (pintype "bidirectional"))
    )
    (net (code "43") (name "/MO9") (class "Default")
      (node (ref "DO2") (pin "2") (pinfunction "2_2") (pintype "bidirectional"))
      (node (ref "IC5") (pin "18") (pinfunction "OUT9_18") (pintype "bidirectional"))
    )
    (net (code "44") (name "/MO10") (class "Default")
      (node (ref "DO2") (pin "3") (pinfunction "3_3") (pintype "bidirectional"))
      (node (ref "IC5") (pin "20") (pinfunction "OUT10_20") (pintype "bidirectional"))
    )
    (net (code "45") (name "/MO11") (class "Default")
      (node (ref "DO2") (pin "4") (pinfunction "4_4") (pintype "bidirectional"))
      (node (ref "IC5") (pin "21") (pinfunction "OUT11_21") (pintype "bidirectional"))
    )
    (net (code "46") (name "/MO12") (class "Default")
      (node (ref "DO2") (pin "5") (pinfunction "5_5") (pintype "bidirectional"))
      (node (ref "IC5") (pin "28") (pinfunction "OUT12_28") (pintype "bidirectional"))
    )
    (net (code "47") (name "/MO13") (class "Default")
      (node (ref "DO2") (pin "6") (pinfunction "6_6") (pintype "bidirectional"))
      (node (ref "IC5") (pin "29") (pinfunction "OUT13_29") (pintype "bidirectional"))
    )
    (net (code "48") (name "/MO14") (class "Default")
      (node (ref "DO2") (pin "7") (pinfunction "7_7") (pintype "bidirectional"))
      (node (ref "IC5") (pin "31") (pinfunction "OUT14_31") (pintype "bidirectional"))
    )
    (net (code "49") (name "/MO15") (class "Default")
      (node (ref "DO2") (pin "8") (pinfunction "8_8") (pintype "bidirectional"))
      (node (ref "IC5") (pin "32") (pinfunction "OUT15_32") (pintype "bidirectional"))
    )
    (net (code "50") (name "/MOD_RX") (class "Default")
      (node (ref "IC4") (pin "7") (pinfunction "RXD_7") (pintype "output"))
      (node (ref "IC8") (pin "36") (pinfunction "RF0_36") (pintype "bidirectional"))
    )
    (net (code "51") (name "/MOD_TX") (class "Default")
      (node (ref "IC4") (pin "4") (pinfunction "TXD_4") (pintype "input"))
      (node (ref "IC8") (pin "37") (pinfunction "RF1_37") (pintype "bidirectional"))
    )
    (net (code "52") (name "/PC_RX2") (class "Default")
      (node (ref "FM_RS") (pin "2") (pinfunction "2_2") (pintype "passive"))
      (node (ref "IC8") (pin "42") (pinfunction "RD0_42") (pintype "bidirectional"))
      (node (ref "OK1") (pin "4") (pinfunction "EMI_4") (pintype "passive"))
      (node (ref "PVP_0") (pin "3") (pinfunction "3_3") (pintype "bidirectional"))
      (node (ref "R36") (pin "2") (pinfunction "2_2") (pintype "passive"))
      (node (ref "TTL_SERIAL") (pin "3") (pinfunction "3_3") (pintype "passive"))
    )
    (net (code "53") (name "/PC_TX2") (class "Default")
      (node (ref "IC1") (pin "1") (pinfunction "T2IN_1") (pintype "input"))
      (node (ref "IC8") (pin "4") (pinfunction "RD6_4") (pintype "bidirectional"))
      (node (ref "OK2") (pin "1") (pinfunction "A_1") (pintype "passive"))
      (node (ref "PVP_0") (pin "8") (pinfunction "8_8") (pintype "bidirectional"))
      (node (ref "TTL_SERIAL") (pin "2") (pinfunction "2_2") (pintype "passive"))
    )
    (net (code "54") (name "/PGC_TICINT") (class "Default")
      (node (ref "EXT_IO") (pin "5") (pinfunction "5_5") (pintype "passive"))
      (node (ref "IC7") (pin "24") (pinfunction "~{INT}_24") (pintype "bidirectional"))
      (node (ref "IC8") (pin "18") (pinfunction "ICSPCLK/RB6_18") (pintype "bidirectional"))
      (node (ref "ICSP") (pin "5") (pinfunction "5_5") (pintype "passive"))
      (node (ref "R26") (pin "2") (pinfunction "2_2") (pintype "passive"))
    )
    (net (code "55") (name "/PGD_DAC1") (class "Default")
      (node (ref "EXT_IO") (pin "6") (pinfunction "6_6") (pintype "passive"))
      (node (ref "IC8") (pin "19") (pinfunction "ICSPDAT/RB7_19") (pintype "bidirectional"))
      (node (ref "ICSP") (pin "4") (pinfunction "4_4") (pintype "passive"))
      (node (ref "SV1") (pin "2") (pinfunction "2_2") (pintype "passive"))
    )
    (net (code "56") (name "/POWERIN") (class "Default")
      (node (ref "F1") (pin "1") (pinfunction "1_1") (pintype "bidirectional"))
      (node (ref "GLORY") (pin "2") (pinfunction "2_2") (pintype "passive"))
    )
    (net (code "57") (name "/RF4") (class "Default")
      (node (ref "AUX_IO") (pin "3") (pinfunction "3_3") (pintype "passive"))
      (node (ref "C35") (pin "1") (pinfunction "1_1") (pintype "passive"))
      (node (ref "IC8") (pin "12") (pinfunction "RF4_12") (pintype "bidirectional"))
    )
    (net (code "58") (name "/RF5") (class "Default")
      (node (ref "AUX_IO") (pin "4") (pinfunction "4_4") (pintype "passive"))
      (node (ref "C32") (pin "1") (pinfunction "1_1") (pintype "passive"))
      (node (ref "IC8") (pin "13") (pinfunction "RF5_13") (pintype "bidirectional"))
    )
    (net (code "59") (name "/RF6") (class "Default")
      (node (ref "AUX_IO") (pin "5") (pinfunction "5_5") (pintype "passive"))
      (node (ref "C33") (pin "1") (pinfunction "1_1") (pintype "passive"))
      (node (ref "IC8") (pin "14") (pinfunction "RF6_14") (pintype "bidirectional"))
    )
    (net (code "60") (name "/RF7") (class "Default")
      (node (ref "AUX_IO") (pin "6") (pinfunction "6_6") (pintype "passive"))
      (node (ref "C34") (pin "1") (pinfunction "1_1") (pintype "passive"))
      (node (ref "IC8") (pin "15") (pinfunction "RF7_15") (pintype "bidirectional"))
    )
    (net (code "61") (name "/RLED") (class "Default")
      (node (ref "IC8") (pin "10") (pinfunction "RB2_10") (pintype "bidirectional"))
      (node (ref "R8") (pin "2") (pinfunction "2_2") (pintype "passive"))
    )
    (net (code "62") (name "/RS232EQRX") (class "Default")
      (node (ref "IC1") (pin "19") (pinfunction "R2IN_19") (pintype "input"))
      (node (ref "SV1") (pin "9") (pinfunction "9_9") (pintype "passive"))
    )
    (net (code "63") (name "/RS232EQTX") (class "Default")
      (node (ref "IC1") (pin "18") (pinfunction "T2OUT_18") (pintype "output"))
      (node (ref "SV1") (pin "10") (pinfunction "10_10") (pintype "passive"))
    )
    (net (code "64") (name "/RS232RX") (class "Default")
      (node (ref "B-NORM") (pin "2") (pinfunction "2_2") (pintype "passive"))
      (node (ref "B-REV") (pin "2") (pinfunction "2_2") (pintype "passive"))
      (node (ref "IC1") (pin "4") (pinfunction "R1IN_4") (pintype "input"))
      (node (ref "R16") (pin "2") (pinfunction "2_2") (pintype "passive"))
      (node (ref "SV1") (pin "7") (pinfunction "7_7") (pintype "passive"))
    )
    (net (code "65") (name "/RS232TX") (class "Default")
      (node (ref "A+NORM") (pin "2") (pinfunction "2_2") (pintype "passive"))
      (node (ref "A+REV") (pin "2") (pinfunction "2_2") (pintype "passive"))
      (node (ref "IC1") (pin "5") (pinfunction "T1OUT_5") (pintype "output"))
      (node (ref "R13") (pin "1") (pinfunction "1_1") (pintype "passive"))
      (node (ref "SV1") (pin "8") (pinfunction "8_8") (pintype "passive"))
    )
    (net (code "66") (name "/RS232_RX_IN") (class "Default")
      (node (ref "A+REV") (pin "1") (pinfunction "1_1") (pintype "passive"))
      (node (ref "B-NORM") (pin "1") (pinfunction "1_1") (pintype "passive"))
      (node (ref "PVP_0") (pin "4") (pinfunction "4_4") (pintype "bidirectional"))
    )
    (net (code "67") (name "/RS232_TX_OUT") (class "Default")
      (node (ref "A+NORM") (pin "1") (pinfunction "1_1") (pintype "passive"))
      (node (ref "B-REV") (pin "1") (pinfunction "1_1") (pintype "passive"))
      (node (ref "PVP_0") (pin "5") (pinfunction "5_5") (pintype "bidirectional"))
    )
    (net (code "68") (name "/R_RESET") (class "Default")
      (node (ref "C1") (pin "1") (pinfunction "1_1") (pintype "passive"))
      (node (ref "C29") (pin "1") (pinfunction "1_1") (pintype "passive"))
      (node (ref "INT_RESET1") (pin "1") (pinfunction "1_1") (pintype "passive"))
      (node (ref "R5") (pin "1") (pinfunction "1_1") (pintype "passive"))
      (node (ref "R6") (pin "1") (pinfunction "1_1") (pintype "passive"))
      (node (ref "RESET") (pin "1") (pinfunction "1_1") (pintype "passive"))
      (node (ref "R_RESET") (pin "2") (pinfunction "2_2") (pintype "passive"))
    )
    (net (code "69") (name "/SCK1") (class "Default")
      (node (ref "DIG_ANA") (pin "4") (pinfunction "4_4") (pintype "passive"))
      (node (ref "DISPLAY") (pin "3") (pinfunction "3_3") (pintype "passive"))
      (node (ref "IC5") (pin "11") (pinfunction "SCLK_11") (pintype "bidirectional"))
      (node (ref "IC7") (pin "16") (pinfunction "SCLK_16") (pintype "bidirectional"))
      (node (ref "IC8") (pin "41") (pinfunction "RC3_41") (pintype "bidirectional"))
    )
    (net (code "70") (name "/SCK2") (class "Default")
      (node (ref "DIG_ANA") (pin "2") (pinfunction "2_2") (pintype "passive"))
      (node (ref "IC6") (pin "6") (pinfunction "2Y_6") (pintype "bidirectional"))
      (node (ref "IC8") (pin "44") (pinfunction "RD2_44") (pintype "bidirectional"))
    )
    (net (code "71") (name "/SCK2_IN") (class "Default")
      (node (ref "IC6") (pin "5") (pinfunction "2A_5") (pintype "bidirectional"))
      (node (ref "R23") (pin "2") (pinfunction "2_2") (pintype "passive"))
    )
    (net (code "72") (name "/SD02_OUT") (class "Default")
      (node (ref "IC6") (pin "3") (pinfunction "1Y_3") (pintype "bidirectional"))
      (node (ref "R21") (pin "2") (pinfunction "2_2") (pintype "passive"))
      (node (ref "SDO2") (pin "1") (pinfunction "1_1") (pintype "passive"))
    )
    (net (code "73") (name "/SDI1") (class "Default")
      (node (ref "DIG_ANA") (pin "5") (pinfunction "5_5") (pintype "passive"))
      (node (ref "DISPLAY") (pin "2") (pinfunction "2_2") (pintype "passive"))
      (node (ref "IC5") (pin "22") (pinfunction "SO_22") (pintype "bidirectional"))
      (node (ref "IC7") (pin "18") (pinfunction "SO_18") (pintype "bidirectional"))
      (node (ref "IC8") (pin "46") (pinfunction "RC4_46") (pintype "bidirectional"))
    )
    (net (code "74") (name "/SDI2") (class "Default")
      (node (ref "EXT_IO") (pin "4") (pinfunction "4_4") (pintype "passive"))
      (node (ref "IC6") (pin "11") (pinfunction "4Y_11") (pintype "bidirectional"))
      (node (ref "IC8") (pin "17") (pinfunction "RB5_17") (pintype "bidirectional"))
      (node (ref "MISC_IO") (pin "6") (pinfunction "6_6") (pintype "passive"))
    )
    (net (code "75") (name "/SDI2_IN") (class "Default")
      (node (ref "IC6") (pin "12") (pinfunction "4A_12") (pintype "bidirectional"))
      (node (ref "R22") (pin "2") (pinfunction "2_2") (pintype "passive"))
    )
    (net (code "76") (name "/SDO1") (class "Default")
      (node (ref "DIG_ANA") (pin "6") (pinfunction "6_6") (pintype "passive"))
      (node (ref "DISPLAY") (pin "4") (pinfunction "4_4") (pintype "passive"))
      (node (ref "IC5") (pin "19") (pinfunction "SI_19") (pintype "bidirectional"))
      (node (ref "IC7") (pin "17") (pinfunction "SI_17") (pintype "bidirectional"))
      (node (ref "IC8") (pin "47") (pinfunction "RC5_47") (pintype "bidirectional"))
    )
    (net (code "77") (name "/SDO2") (class "Default")
      (node (ref "IC6") (pin "2") (pinfunction "1A_2") (pintype "bidirectional"))
      (node (ref "IC8") (pin "16") (pinfunction "RB4_16") (pintype "bidirectional"))
    )
    (net (code "78") (name "/SPI2_REQ") (class "Default")
      (node (ref "IC8") (pin "8") (pinfunction "RB0_8") (pintype "bidirectional"))
      (node (ref "R20") (pin "2") (pinfunction "2_2") (pintype "passive"))
      (node (ref "R31") (pin "1") (pinfunction "1_1") (pintype "passive"))
    )
    (net (code "79") (name "/SS2") (class "Default")
      (node (ref "DIG_ANA") (pin "1") (pinfunction "1_1") (pintype "passive"))
      (node (ref "IC6") (pin "8") (pinfunction "3Y_8") (pintype "bidirectional"))
      (node (ref "IC8") (pin "43") (pinfunction "RD1_43") (pintype "bidirectional"))
    )
    (net (code "80") (name "/SS2_IN") (class "Default")
      (node (ref "IC6") (pin "9") (pinfunction "3A_9") (pintype "bidirectional"))
      (node (ref "R24") (pin "2") (pinfunction "2_2") (pintype "passive"))
      (node (ref "R30") (pin "2") (pinfunction "2_2") (pintype "passive"))
    )
    (net (code "81") (name "/SS_CS") (class "Default")
      (node (ref "IC8") (pin "29") (pinfunction "RE2_29") (pintype "bidirectional"))
      (node (ref "MISC_IO") (pin "3") (pinfunction "3_3") (pintype "passive"))
    )
    (net (code "82") (name "/TIC0") (class "Default")
      (node (ref "IC7") (pin "13") (pinfunction "IN0_13") (pintype "bidirectional"))
      (node (ref "TIC0_7") (pin "1") (pinfunction "1_1") (pintype "bidirectional"))
    )
    (net (code "83") (name "/TIC1") (class "Default")
      (node (ref "IC7") (pin "14") (pinfunction "IN1_14") (pintype "bidirectional"))
      (node (ref "TIC0_7") (pin "2") (pinfunction "2_2") (pintype "bidirectional"))
    )
    (net (code "84") (name "/TIC2") (class "Default")
      (node (ref "IC7") (pin "25") (pinfunction "IN2_25") (pintype "bidirectional"))
      (node (ref "TIC0_7") (pin "3") (pinfunction "3_3") (pintype "bidirectional"))
    )
    (net (code "85") (name "/TIC3") (class "Default")
      (node (ref "IC7") (pin "26") (pinfunction "IN3_26") (pintype "bidirectional"))
      (node (ref "TIC0_7") (pin "4") (pinfunction "4_4") (pintype "bidirectional"))
    )
    (net (code "86") (name "/TIC4") (class "Default")
      (node (ref "IC7") (pin "27") (pinfunction "IN4_27") (pintype "bidirectional"))
      (node (ref "TIC0_7") (pin "5") (pinfunction "5_5") (pintype "bidirectional"))
    )
    (net (code "87") (name "/TIC5") (class "Default")
      (node (ref "IC7") (pin "29") (pinfunction "IN5_29") (pintype "bidirectional"))
      (node (ref "TIC0_7") (pin "6") (pinfunction "6_6") (pintype "bidirectional"))
    )
    (net (code "88") (name "/TIC6") (class "Default")
      (node (ref "IC7") (pin "30") (pinfunction "IN6_30") (pintype "bidirectional"))
      (node (ref "TIC0_7") (pin "7") (pinfunction "7_7") (pintype "bidirectional"))
    )
    (net (code "89") (name "/TIC7") (class "Default")
      (node (ref "IC7") (pin "31") (pinfunction "IN7_31") (pintype "bidirectional"))
      (node (ref "TIC0_7") (pin "8") (pinfunction "8_8") (pintype "bidirectional"))
    )
    (net (code "90") (name "/TIC8") (class "Default")
      (node (ref "IC7") (pin "32") (pinfunction "IN8_32") (pintype "bidirectional"))
      (node (ref "R28") (pin "2") (pinfunction "2_2") (pintype "passive"))
      (node (ref "TIC8_15") (pin "1") (pinfunction "1_1") (pintype "bidirectional"))
    )
    (net (code "91") (name "/TIC9") (class "Default")
      (node (ref "IC7") (pin "33") (pinfunction "IN9_33") (pintype "bidirectional"))
      (node (ref "R29") (pin "2") (pinfunction "2_2") (pintype "passive"))
      (node (ref "TIC8_15") (pin "2") (pinfunction "2_2") (pintype "bidirectional"))
    )
    (net (code "92") (name "/TIC10") (class "Default")
      (node (ref "IC7") (pin "34") (pinfunction "IN10_34") (pintype "bidirectional"))
      (node (ref "TIC8_15") (pin "3") (pinfunction "3_3") (pintype "bidirectional"))
    )
    (net (code "93") (name "/TIC11") (class "Default")
      (node (ref "IC7") (pin "35") (pinfunction "IN11_35") (pintype "bidirectional"))
      (node (ref "TIC8_15") (pin "4") (pinfunction "4_4") (pintype "bidirectional"))
    )
    (net (code "94") (name "/TIC12") (class "Default")
      (node (ref "IC7") (pin "36") (pinfunction "IN12_36") (pintype "bidirectional"))
      (node (ref "TIC8_15") (pin "5") (pinfunction "5_5") (pintype "bidirectional"))
    )
    (net (code "95") (name "/TIC13") (class "Default")
      (node (ref "IC7") (pin "1") (pinfunction "IN13_1") (pintype "bidirectional"))
      (node (ref "TIC8_15") (pin "6") (pinfunction "6_6") (pintype "bidirectional"))
    )
    (net (code "96") (name "/TIC14") (class "Default")
      (node (ref "IC7") (pin "2") (pinfunction "IN14_2") (pintype "bidirectional"))
      (node (ref "TIC8_15") (pin "7") (pinfunction "7_7") (pintype "bidirectional"))
    )
    (net (code "97") (name "/TIC15") (class "Default")
      (node (ref "IC7") (pin "3") (pinfunction "IN15_3") (pintype "bidirectional"))
      (node (ref "TIC8_15") (pin "8") (pinfunction "8_8") (pintype "bidirectional"))
    )
    (net (code "98") (name "/TIC16") (class "Default")
      (node (ref "IC7") (pin "4") (pinfunction "IN16_4") (pintype "bidirectional"))
      (node (ref "TIC16_23") (pin "1") (pinfunction "1_1") (pintype "bidirectional"))
    )
    (net (code "99") (name "/TIC17") (class "Default")
      (node (ref "IC7") (pin "5") (pinfunction "IN17_5") (pintype "bidirectional"))
      (node (ref "TIC16_23") (pin "2") (pinfunction "2_2") (pintype "bidirectional"))
    )
    (net (code "100") (name "/TIC18") (class "Default")
      (node (ref "IC7") (pin "6") (pinfunction "IN18_6") (pintype "bidirectional"))
      (node (ref "TIC16_23") (pin "3") (pinfunction "3_3") (pintype "bidirectional"))
    )
    (net (code "101") (name "/TIC19") (class "Default")
      (node (ref "IC7") (pin "7") (pinfunction "IN19_7") (pintype "bidirectional"))
      (node (ref "TIC16_23") (pin "4") (pinfunction "4_4") (pintype "bidirectional"))
    )
    (net (code "102") (name "/TIC20") (class "Default")
      (node (ref "IC7") (pin "8") (pinfunction "IN20_8") (pintype "bidirectional"))
      (node (ref "TIC16_23") (pin "5") (pinfunction "5_5") (pintype "bidirectional"))
    )
    (net (code "103") (name "/TIC21") (class "Default")
      (node (ref "IC7") (pin "10") (pinfunction "IN21_10") (pintype "bidirectional"))
      (node (ref "TIC16_23") (pin "6") (pinfunction "6_6") (pintype "bidirectional"))
    )
    (net (code "104") (name "/TIC22") (class "Default")
      (node (ref "IC7") (pin "11") (pinfunction "IN22_11") (pintype "bidirectional"))
      (node (ref "TIC16_23") (pin "7") (pinfunction "7_7") (pintype "bidirectional"))
    )
    (net (code "105") (name "/TIC23") (class "Default")
      (node (ref "IC7") (pin "12") (pinfunction "IN23_12") (pintype "bidirectional"))
      (node (ref "TIC16_23") (pin "8") (pinfunction "8_8") (pintype "bidirectional"))
    )
    (net (code "106") (name "/TIC_CS") (class "Default")
      (node (ref "IC7") (pin "15") (pinfunction "~{CS}_15") (pintype "bidirectional"))
      (node (ref "IC8") (pin "28") (pinfunction "RE1_28") (pintype "bidirectional"))
      (node (ref "MISC_IO") (pin "2") (pinfunction "2_2") (pintype "passive"))
    )
    (net (code "107") (name "/TP1_TEST_SIG") (class "Default")
      (node (ref "IC8") (pin "40") (pinfunction "RC2_40") (pintype "bidirectional"))
      (node (ref "TP1") (pin "TP") (pinfunction "TP_TP") (pintype "input"))
    )
    (net (code "108") (name "/TXD3") (class "Default")
      (node (ref "IC8") (pin "38") (pinfunction "RF2_38") (pintype "bidirectional"))
      (node (ref "TXDE3") (pin "2") (pinfunction "2_2") (pintype "passive"))
    )
    (net (code "109") (name "/VPOWER") (class "Default")
      (node (ref "IC5") (pin "6") (pinfunction "VPWR_6") (pintype "bidirectional"))
      (node (ref "VDD-TIC") (pin "2") (pinfunction "2_2") (pintype "passive"))
    )
    (net (code "110") (name "/VREF_4.1") (class "Default")
      (node (ref "ANALOG") (pin "3") (pinfunction "3_3") (pintype "passive"))
      (node (ref "C14") (pin "1") (pinfunction "1_1") (pintype "passive"))
      (node (ref "C15") (pin "1") (pinfunction "1_1") (pintype "passive"))
      (node (ref "IC2") (pin "6") (pinfunction "VOUT_6") (pintype "bidirectional"))
      (node (ref "IC8") (pin "24") (pinfunction "RA3_24") (pintype "bidirectional"))
    )
    (net (code "111") (name "0V") (class "Default")
      (node (ref "LED5") (pin "C") (pinfunction "C_C") (pintype "passive"))
      (node (ref "MATE") (pin "2") (pinfunction "2_2") (pintype "passive"))
      (node (ref "R34") (pin "2") (pinfunction "2_2") (pintype "passive"))
      (node (ref "R35") (pin "1") (pinfunction "1_1") (pintype "passive"))
    )
    (net (code "112") (name "GND") (class "Default")
      (node (ref "C10") (pin "2") (pinfunction "2_2") (pintype "passive"))
      (node (ref "C9") (pin "2") (pinfunction "2_2") (pintype "passive"))
      (node (ref "R18") (pin "2") (pinfunction "2_2") (pintype "passive"))
    )
    (net (code "113") (name "Net-(IC1A-C2+{slash}1)") (class "Default")
      (node (ref "IC1") (pin "12") (pinfunction "C2+/1_12") (pintype "passive"))
      (node (ref "IC1") (pin "15") (pinfunction "C2+/2_15") (pintype "passive"))
    )
    (net (code "114") (name "Net-(IC1A-C2-{slash}1)") (class "Default")
      (node (ref "IC1") (pin "11") (pinfunction "C2-/1_11") (pintype "passive"))
      (node (ref "IC1") (pin "16") (pinfunction "C2-/2_16") (pintype "passive"))
    )
    (net (code "115") (name "Net-(IC1A-R2OUT)") (class "Default")
      (node (ref "FM_RS") (pin "1") (pinfunction "1_1") (pintype "passive"))
      (node (ref "IC1") (pin "20") (pinfunction "R2OUT_20") (pintype "output"))
    )
    (net (code "116") (name "Net-(IC1A-V-{slash}1)") (class "Default")
      (node (ref "IC1") (pin "10") (pinfunction "V-/1_10") (pintype "passive"))
      (node (ref "IC1") (pin "17") (pinfunction "V-/2_17") (pintype "passive"))
    )
    (net (code "117") (name "Net-(IC7-CAP_A)") (class "Default")
      (node (ref "C24") (pin "1") (pinfunction "1_1") (pintype "passive"))
      (node (ref "IC7") (pin "20") (pinfunction "CAP_A_20") (pintype "bidirectional"))
    )
    (net (code "118") (name "Net-(IC7-CAP_D)") (class "Default")
      (node (ref "C23") (pin "1") (pinfunction "1_1") (pintype "passive"))
      (node (ref "IC7") (pin "23") (pinfunction "CAP_D_23") (pintype "bidirectional"))
    )
    (net (code "119") (name "Net-(IC7-CAP_PRE)") (class "Default")
      (node (ref "C25") (pin "1") (pinfunction "1_1") (pintype "passive"))
      (node (ref "IC7") (pin "22") (pinfunction "CAP_PRE_22") (pintype "bidirectional"))
    )
    (net (code "120") (name "Net-(LED1_RED-PadA)") (class "Default")
      (node (ref "LED1_RED") (pin "A") (pinfunction "A_A") (pintype "passive"))
      (node (ref "R7") (pin "1") (pinfunction "1_1") (pintype "passive"))
    )
    (net (code "121") (name "Net-(LED2-PadA)") (class "Default")
      (node (ref "LED2") (pin "A") (pinfunction "A_A") (pintype "passive"))
      (node (ref "R8") (pin "1") (pinfunction "1_1") (pintype "passive"))
    )
    (net (code "122") (name "Net-(LED3-PadA)") (class "Default")
      (node (ref "LED3") (pin "A") (pinfunction "A_A") (pintype "passive"))
      (node (ref "R9") (pin "1") (pinfunction "1_1") (pintype "passive"))
    )
    (net (code "123") (name "Net-(LED4-PadA)") (class "Default")
      (node (ref "LED4") (pin "A") (pinfunction "A_A") (pintype "passive"))
      (node (ref "R19") (pin "2") (pinfunction "2_2") (pintype "passive"))
    )
    (net (code "124") (name "Net-(LED5-PadA)") (class "Default")
      (node (ref "LED5") (pin "A") (pinfunction "A_A") (pintype "passive"))
      (node (ref "R38") (pin "2") (pinfunction "2_2") (pintype "passive"))
    )
    (net (code "125") (name "Net-(OK1-C)") (class "Default")
      (node (ref "OK1") (pin "2") (pinfunction "C_2") (pintype "passive"))
      (node (ref "R34") (pin "1") (pinfunction "1_1") (pintype "passive"))
    )
    (net (code "126") (name "Net-(OK2-C)") (class "Default")
      (node (ref "OK2") (pin "2") (pinfunction "C_2") (pintype "passive"))
      (node (ref "R37") (pin "1") (pinfunction "1_1") (pintype "passive"))
    )
    (net (code "127") (name "Net-(R1-Pad1)") (class "Default")
      (node (ref "R1") (pin "1") (pinfunction "1_1") (pintype "passive"))
      (node (ref "SV1") (pin "3") (pinfunction "3_3") (pintype "passive"))
      (node (ref "SV1") (pin "4") (pinfunction "4_4") (pintype "passive"))
    )
    (net (code "128") (name "Net-(R20-Pad1)") (class "Default")
      (node (ref "R20") (pin "1") (pinfunction "1_1") (pintype "passive"))
      (node (ref "SPI2") (pin "6") (pinfunction "6_6") (pintype "passive"))
    )
    (net (code "129") (name "Net-(R21-Pad1)") (class "Default")
      (node (ref "R21") (pin "1") (pinfunction "1_1") (pintype "passive"))
      (node (ref "SPI2") (pin "5") (pinfunction "5_5") (pintype "passive"))
    )
    (net (code "130") (name "Net-(R22-Pad1)") (class "Default")
      (node (ref "R22") (pin "1") (pinfunction "1_1") (pintype "passive"))
      (node (ref "SPI2") (pin "4") (pinfunction "4_4") (pintype "passive"))
    )
    (net (code "131") (name "Net-(R23-Pad1)") (class "Default")
      (node (ref "R23") (pin "1") (pinfunction "1_1") (pintype "passive"))
      (node (ref "SPI2") (pin "3") (pinfunction "3_3") (pintype "passive"))
    )
    (net (code "132") (name "Net-(R24-Pad1)") (class "Default")
      (node (ref "R24") (pin "1") (pinfunction "1_1") (pintype "passive"))
      (node (ref "SPI2") (pin "2") (pinfunction "2_2") (pintype "passive"))
    )
    (net (code "133") (name "VCC") (class "Default")
      (node (ref "C10") (pin "1") (pinfunction "1_1") (pintype "passive"))
      (node (ref "C2") (pin "1") (pinfunction "1_1") (pintype "passive"))
      (node (ref "C9") (pin "1") (pinfunction "1_1") (pintype "passive"))
      (node (ref "R17") (pin "2") (pinfunction "2_2") (pintype "passive"))
      (node (ref "SHORT_VV") (pin "2") (pinfunction "2_2") (pintype "passive"))
    )
    (net (code "134") (name "VDD") (class "Default")
      (node (ref "ANALOG") (pin "8") (pinfunction "8_8") (pintype "passive"))
      (node (ref "AUX_IO") (pin "2") (pinfunction "2_2") (pintype "passive"))
      (node (ref "C11") (pin "1") (pinfunction "1_1") (pintype "passive"))
      (node (ref "C12") (pin "1") (pinfunction "1_1") (pintype "passive"))
      (node (ref "C13") (pin "1") (pinfunction "1_1") (pintype "passive"))
      (node (ref "C18") (pin "1") (pinfunction "1_1") (pintype "passive"))
      (node (ref "C19") (pin "1") (pinfunction "1_1") (pintype "passive"))
      (node (ref "C21") (pin "1") (pinfunction "1_1") (pintype "passive"))
      (node (ref "C22") (pin "1") (pinfunction "1_1") (pintype "passive"))
      (node (ref "C28") (pin "1") (pinfunction "1_1") (pintype "passive"))
      (node (ref "C3") (pin "1") (pinfunction "1_1") (pintype "passive"))
      (node (ref "C30") (pin "1") (pinfunction "1_1") (pintype "passive"))
      (node (ref "C31") (pin "1") (pinfunction "1_1") (pintype "passive"))
      (node (ref "C36") (pin "1") (pinfunction "1_1") (pintype "passive"))
      (node (ref "C4") (pin "1") (pinfunction "1_1") (pintype "passive"))
      (node (ref "C5") (pin "1") (pinfunction "1_1") (pintype "passive"))
      (node (ref "C6") (pin "1") (pinfunction "1_1") (pintype "passive"))
      (node (ref "C7") (pin "1") (pinfunction "1_1") (pintype "passive"))
      (node (ref "C8") (pin "1") (pinfunction "1_1") (pintype "passive"))
      (node (ref "DIG_ANA") (pin "8") (pinfunction "8_8") (pintype "passive"))
      (node (ref "DISPLAY") (pin "6") (pinfunction "6_6") (pintype "passive"))
      (node (ref "DO1") (pin "9") (pinfunction "9_9") (pintype "bidirectional"))
      (node (ref "DO2") (pin "9") (pinfunction "9_9") (pintype "bidirectional"))
      (node (ref "F1") (pin "2") (pinfunction "2_2") (pintype "bidirectional"))
      (node (ref "IC2") (pin "4") (pinfunction "IN_4") (pintype "bidirectional"))
      (node (ref "IC3") (pin "1") (pinfunction "VIN_1") (pintype "bidirectional"))
      (node (ref "IC3") (pin "3") (pinfunction "EN_3") (pintype "bidirectional"))
      (node (ref "IC4") (pin "2") (pinfunction "VCC_2") (pintype "power_in"))
      (node (ref "IC4") (pin "3") (pinfunction "VIO_3") (pintype "power_in"))
      (node (ref "IC5") (pin "3") (pinfunction "SOPWR_3") (pintype "bidirectional"))
      (node (ref "IC7") (pin "19") (pinfunction "VDD_19") (pintype "bidirectional"))
      (node (ref "IC8") (pin "30") (pinfunction "VDD_2_30") (pintype "bidirectional"))
      (node (ref "IC8") (pin "7") (pinfunction "VDD_1_7") (pintype "bidirectional"))
      (node (ref "ICSP") (pin "2") (pinfunction "2_2") (pintype "passive"))
      (node (ref "MODBUS") (pin "5") (pinfunction "5_5") (pintype "passive"))
      (node (ref "OK1") (pin "5") (pinfunction "COL_5") (pintype "passive"))
      (node (ref "OS1_16MHZ") (pin "1") (pinfunction "CON_1") (pintype "input"))
      (node (ref "OS1_16MHZ") (pin "4") (pinfunction "VDD_4") (pintype "power_in"))
      (node (ref "PVP_0") (pin "1") (pinfunction "1_1") (pintype "bidirectional"))
      (node (ref "R1") (pin "2") (pinfunction "2_2") (pintype "passive"))
      (node (ref "R14") (pin "1") (pinfunction "1_1") (pintype "passive"))
      (node (ref "R17") (pin "1") (pinfunction "1_1") (pintype "passive"))
      (node (ref "R19") (pin "1") (pinfunction "1_1") (pintype "passive"))
      (node (ref "R25") (pin "1") (pinfunction "1_1") (pintype "passive"))
      (node (ref "R26") (pin "1") (pinfunction "1_1") (pintype "passive"))
      (node (ref "R3") (pin "2") (pinfunction "2_2") (pintype "passive"))
      (node (ref "R33") (pin "2") (pinfunction "2_2") (pintype "passive"))
      (node (ref "R6") (pin "2") (pinfunction "2_2") (pintype "passive"))
      (node (ref "SHORT_VV") (pin "1") (pinfunction "1_1") (pintype "passive"))
      (node (ref "TIC_DIGITAL") (pin "4") (pinfunction "4_4") (pintype "passive"))
      (node (ref "TTL_SERIAL") (pin "4") (pinfunction "4_4") (pintype "passive"))
      (node (ref "VDD-TIC") (pin "1") (pinfunction "1_1") (pintype "passive"))
      (node (ref "ZENER") (pin "C") (pinfunction "C_C") (pintype "passive"))
    )
    (net (code "135") (name "VSS") (class "Default")
      (node (ref "3.3V_PWR") (pin "1") (pinfunction "1_1") (pintype "passive"))
      (node (ref "ANALOG") (pin "9") (pinfunction "9_9") (pintype "passive"))
      (node (ref "AUX_IO") (pin "1") (pinfunction "1_1") (pintype "passive"))
      (node (ref "C1") (pin "2") (pinfunction "2_2") (pintype "passive"))
      (node (ref "C11") (pin "2") (pinfunction "2_2") (pintype "passive"))
      (node (ref "C12") (pin "2") (pinfunction "2_2") (pintype "passive"))
      (node (ref "C13") (pin "2") (pinfunction "2_2") (pintype "passive"))
      (node (ref "C14") (pin "2") (pinfunction "2_2") (pintype "passive"))
      (node (ref "C15") (pin "2") (pinfunction "2_2") (pintype "passive"))
      (node (ref "C16") (pin "2") (pinfunction "2_2") (pintype "passive"))
      (node (ref "C17") (pin "2") (pinfunction "2_2") (pintype "passive"))
      (node (ref "C18") (pin "2") (pinfunction "2_2") (pintype "passive"))
      (node (ref "C19") (pin "2") (pinfunction "2_2") (pintype "passive"))
      (node (ref "C2") (pin "2") (pinfunction "2_2") (pintype "passive"))
      (node (ref "C20") (pin "2") (pinfunction "2_2") (pintype "passive"))
      (node (ref "C21") (pin "2") (pinfunction "2_2") (pintype "passive"))
      (node (ref "C22") (pin "2") (pinfunction "2_2") (pintype "passive"))
      (node (ref "C23") (pin "2") (pinfunction "2_2") (pintype "passive"))
      (node (ref "C24") (pin "2") (pinfunction "2_2") (pintype "passive"))
      (node (ref "C25") (pin "2") (pinfunction "2_2") (pintype "passive"))
      (node (ref "C26") (pin "2") (pinfunction "2_2") (pintype "passive"))
      (node (ref "C27") (pin "2") (pinfunction "2_2") (pintype "passive"))
      (node (ref "C28") (pin "2") (pinfunction "2_2") (pintype "passive"))
      (node (ref "C29") (pin "2") (pinfunction "2_2") (pintype "passive"))
      (node (ref "C3") (pin "2") (pinfunction "2_2") (pintype "passive"))
      (node (ref "C30") (pin "2") (pinfunction "2_2") (pintype "passive"))
      (node (ref "C31") (pin "2") (pinfunction "2_2") (pintype "passive"))
      (node (ref "C32") (pin "2") (pinfunction "2_2") (pintype "passive"))
      (node (ref "C33") (pin "2") (pinfunction "2_2") (pintype "passive"))
      (node (ref "C34") (pin "2") (pinfunction "2_2") (pintype "passive"))
      (node (ref "C35") (pin "2") (pinfunction "2_2") (pintype "passive"))
      (node (ref "C36") (pin "2") (pinfunction "2_2") (pintype "passive"))
      (node (ref "C4") (pin "2") (pinfunction "2_2") (pintype "passive"))
      (node (ref "C5") (pin "2") (pinfunction "2_2") (pintype "passive"))
      (node (ref "C6") (pin "2") (pinfunction "2_2") (pintype "passive"))
      (node (ref "C7") (pin "2") (pinfunction "2_2") (pintype "passive"))
      (node (ref "C8") (pin "2") (pinfunction "2_2") (pintype "passive"))
      (node (ref "DIG_ANA") (pin "9") (pinfunction "9_9") (pintype "passive"))
      (node (ref "DISPLAY") (pin "5") (pinfunction "5_5") (pintype "passive"))
      (node (ref "DO1") (pin "10") (pinfunction "10_10") (pintype "bidirectional"))
      (node (ref "DO2") (pin "10") (pinfunction "10_10") (pintype "bidirectional"))
      (node (ref "EXT_IO") (pin "1") (pinfunction "1_1") (pintype "passive"))
      (node (ref "GLORY") (pin "1") (pinfunction "1_1") (pintype "passive"))
      (node (ref "IC2") (pin "2") (pinfunction "GND_2") (pintype "bidirectional"))
      (node (ref "IC3") (pin "2") (pinfunction "GND_2") (pintype "bidirectional"))
      (node (ref "IC4") (pin "1") (pinfunction "GND_1_1") (pintype "power_in"))
      (node (ref "IC4") (pin "10") (pinfunction "GND_4_10") (pintype "power_in"))
      (node (ref "IC4") (pin "12") (pinfunction "GND_5_12") (pintype "power_in"))
      (node (ref "IC4") (pin "13") (pinfunction "GND_6_13") (pintype "power_in"))
      (node (ref "IC4") (pin "15") (pinfunction "GND_7_15") (pintype "power_in"))
      (node (ref "IC4") (pin "16") (pinfunction "GND_8_16") (pintype "power_in"))
      (node (ref "IC4") (pin "8") (pinfunction "GND_2_8") (pintype "power_in"))
      (node (ref "IC4") (pin "9") (pinfunction "GND_3_9") (pintype "power_in"))
      (node (ref "IC5") (pin "10") (pinfunction "GND_4_10") (pintype "bidirectional"))
      (node (ref "IC5") (pin "23") (pinfunction "GND_5_23") (pintype "bidirectional"))
      (node (ref "IC5") (pin "24") (pinfunction "GND_6_24") (pintype "bidirectional"))
      (node (ref "IC5") (pin "25") (pinfunction "GND_7_25") (pintype "bidirectional"))
      (node (ref "IC5") (pin "26") (pinfunction "GND_8_26") (pintype "bidirectional"))
      (node (ref "IC5") (pin "33") (pinfunction "EP_33") (pintype "bidirectional"))
      (node (ref "IC5") (pin "7") (pinfunction "GND_1_7") (pintype "bidirectional"))
      (node (ref "IC5") (pin "8") (pinfunction "GND_2_8") (pintype "bidirectional"))
      (node (ref "IC5") (pin "9") (pinfunction "GND_3_9") (pintype "bidirectional"))
      (node (ref "IC6") (pin "1") (pinfunction "1~{G}_1") (pintype "bidirectional"))
      (node (ref "IC6") (pin "10") (pinfunction "3~{G}_10") (pintype "bidirectional"))
      (node (ref "IC6") (pin "13") (pinfunction "4~{G}_13") (pintype "bidirectional"))
      (node (ref "IC6") (pin "4") (pinfunction "2~{G}_4") (pintype "bidirectional"))
      (node (ref "IC6") (pin "7") (pinfunction "GND_7") (pintype "bidirectional"))
      (node (ref "IC7") (pin "21") (pinfunction "RESET_21") (pintype "bidirectional"))
      (node (ref "IC7") (pin "28") (pinfunction "DGND_28") (pintype "bidirectional"))
      (node (ref "IC7") (pin "39") (pinfunction "EP_39") (pintype "bidirectional"))
      (node (ref "IC7") (pin "9") (pinfunction "AGND_9") (pintype "bidirectional"))
      (node (ref "IC8") (pin "31") (pinfunction "VSS_2_31") (pintype "bidirectional"))
      (node (ref "IC8") (pin "49") (pinfunction "EP_49") (pintype "bidirectional"))
      (node (ref "IC8") (pin "6") (pinfunction "VSS_1_6") (pintype "bidirectional"))
      (node (ref "ICSP") (pin "3") (pinfunction "3_3") (pintype "passive"))
      (node (ref "LED1_RED") (pin "C") (pinfunction "C_C") (pintype "passive"))
      (node (ref "LED2") (pin "C") (pinfunction "C_C") (pintype "passive"))
      (node (ref "LED3") (pin "C") (pinfunction "C_C") (pintype "passive"))
      (node (ref "LED4") (pin "C") (pinfunction "C_C") (pintype "passive"))
      (node (ref "MISC_IO") (pin "9") (pinfunction "9_9") (pintype "passive"))
      (node (ref "MODBUS") (pin "1") (pinfunction "1_1") (pintype "passive"))
      (node (ref "MODBUS") (pin "4") (pinfunction "4_4") (pintype "passive"))
      (node (ref "OS1_16MHZ") (pin "2") (pinfunction "VSS_2") (pintype "power_in"))
      (node (ref "PVP_0") (pin "10") (pinfunction "MH2_10") (pintype "bidirectional"))
      (node (ref "PVP_0") (pin "6") (pinfunction "6_6") (pintype "bidirectional"))
      (node (ref "PVP_0") (pin "9") (pinfunction "MH1_9") (pintype "bidirectional"))
      (node (ref "R10") (pin "1") (pinfunction "1_1") (pintype "passive"))
      (node (ref "R12") (pin "1") (pinfunction "1_1") (pintype "passive"))
      (node (ref "R15") (pin "2") (pinfunction "2_2") (pintype "passive"))
      (node (ref "R18") (pin "1") (pinfunction "1_1") (pintype "passive"))
      (node (ref "R32") (pin "1") (pinfunction "1_1") (pintype "passive"))
      (node (ref "R36") (pin "1") (pinfunction "1_1") (pintype "passive"))
      (node (ref "R37") (pin "2") (pinfunction "2_2") (pintype "passive"))
      (node (ref "R39") (pin "1") (pinfunction "1_1") (pintype "passive"))
      (node (ref "R4") (pin "1") (pinfunction "1_1") (pintype "passive"))
      (node (ref "RESET") (pin "2") (pinfunction "2_2") (pintype "passive"))
      (node (ref "R_RESET") (pin "1") (pinfunction "1_1") (pintype "passive"))
      (node (ref "SPI2") (pin "1") (pinfunction "1_1") (pintype "passive"))
      (node (ref "SV1") (pin "1") (pinfunction "1_1") (pintype "passive"))
      (node (ref "SV1") (pin "5") (pinfunction "5_5") (pintype "passive"))
      (node (ref "SV1") (pin "6") (pinfunction "6_6") (pintype "passive"))
      (node (ref "TIC0_7") (pin "10") (pinfunction "10_10") (pintype "bidirectional"))
      (node (ref "TIC16_23") (pin "10") (pinfunction "10_10") (pintype "bidirectional"))
      (node (ref "TIC8_15") (pin "10") (pinfunction "10_10") (pintype "bidirectional"))
      (node (ref "TIC_DIGITAL") (pin "1") (pinfunction "1_1") (pintype "passive"))
      (node (ref "TTL_SERIAL") (pin "1") (pinfunction "1_1") (pintype "passive"))
      (node (ref "VS_TIC_PWR") (pin "1") (pinfunction "1_1") (pintype "passive"))
      (node (ref "Z1") (pin "2") (pinfunction "A_2") (pintype "bidirectional"))
      (node (ref "Z2") (pin "2") (pinfunction "A_2") (pintype "bidirectional"))
      (node (ref "ZENER") (pin "A") (pinfunction "A_A") (pintype "passive"))
    )
    (net (code "136") (name "unconnected-(IC1A-C1+-Pad13)") (class "Default")
      (node (ref "IC1") (pin "13") (pinfunction "C1+_13") (pintype "passive"))
    )
    (net (code "137") (name "unconnected-(IC1A-C1--Pad14)") (class "Default")
      (node (ref "IC1") (pin "14") (pinfunction "C1-_14") (pintype "passive"))
    )
    (net (code "138") (name "unconnected-(IC1A-V+-Pad8)") (class "Default")
      (node (ref "IC1") (pin "8") (pinfunction "V+_8") (pintype "passive"))
    )
    (net (code "139") (name "unconnected-(IC2-NC_1-Pad1)") (class "Default")
      (node (ref "IC2") (pin "1") (pinfunction "NC_1_1") (pintype "bidirectional"))
    )
    (net (code "140") (name "unconnected-(IC2-NC_2-Pad3)") (class "Default")
      (node (ref "IC2") (pin "3") (pinfunction "NC_2_3") (pintype "bidirectional"))
    )
    (net (code "141") (name "unconnected-(IC2-NC_3-Pad5)") (class "Default")
      (node (ref "IC2") (pin "5") (pinfunction "NC_3_5") (pintype "bidirectional"))
    )
    (net (code "142") (name "unconnected-(IC3-NC-Pad4)") (class "Default")
      (node (ref "IC3") (pin "4") (pinfunction "NC_4") (pintype "no_connect"))
    )
    (net (code "143") (name "unconnected-(ICSP-Pad6)") (class "Default")
      (node (ref "ICSP") (pin "6") (pinfunction "6_6") (pintype "passive"))
    )
    (net (code "144") (name "unconnected-(OK1-BAS-Pad6)") (class "Default")
      (node (ref "OK1") (pin "6") (pinfunction "BAS_6") (pintype "passive"))
    )
    (net (code "145") (name "unconnected-(OK2-BAS-Pad6)") (class "Default")
      (node (ref "OK2") (pin "6") (pinfunction "BAS_6") (pintype "passive"))
    )
  )
)
